# Controller.net
KiCad netlist of a schematic drawn in EAGLE
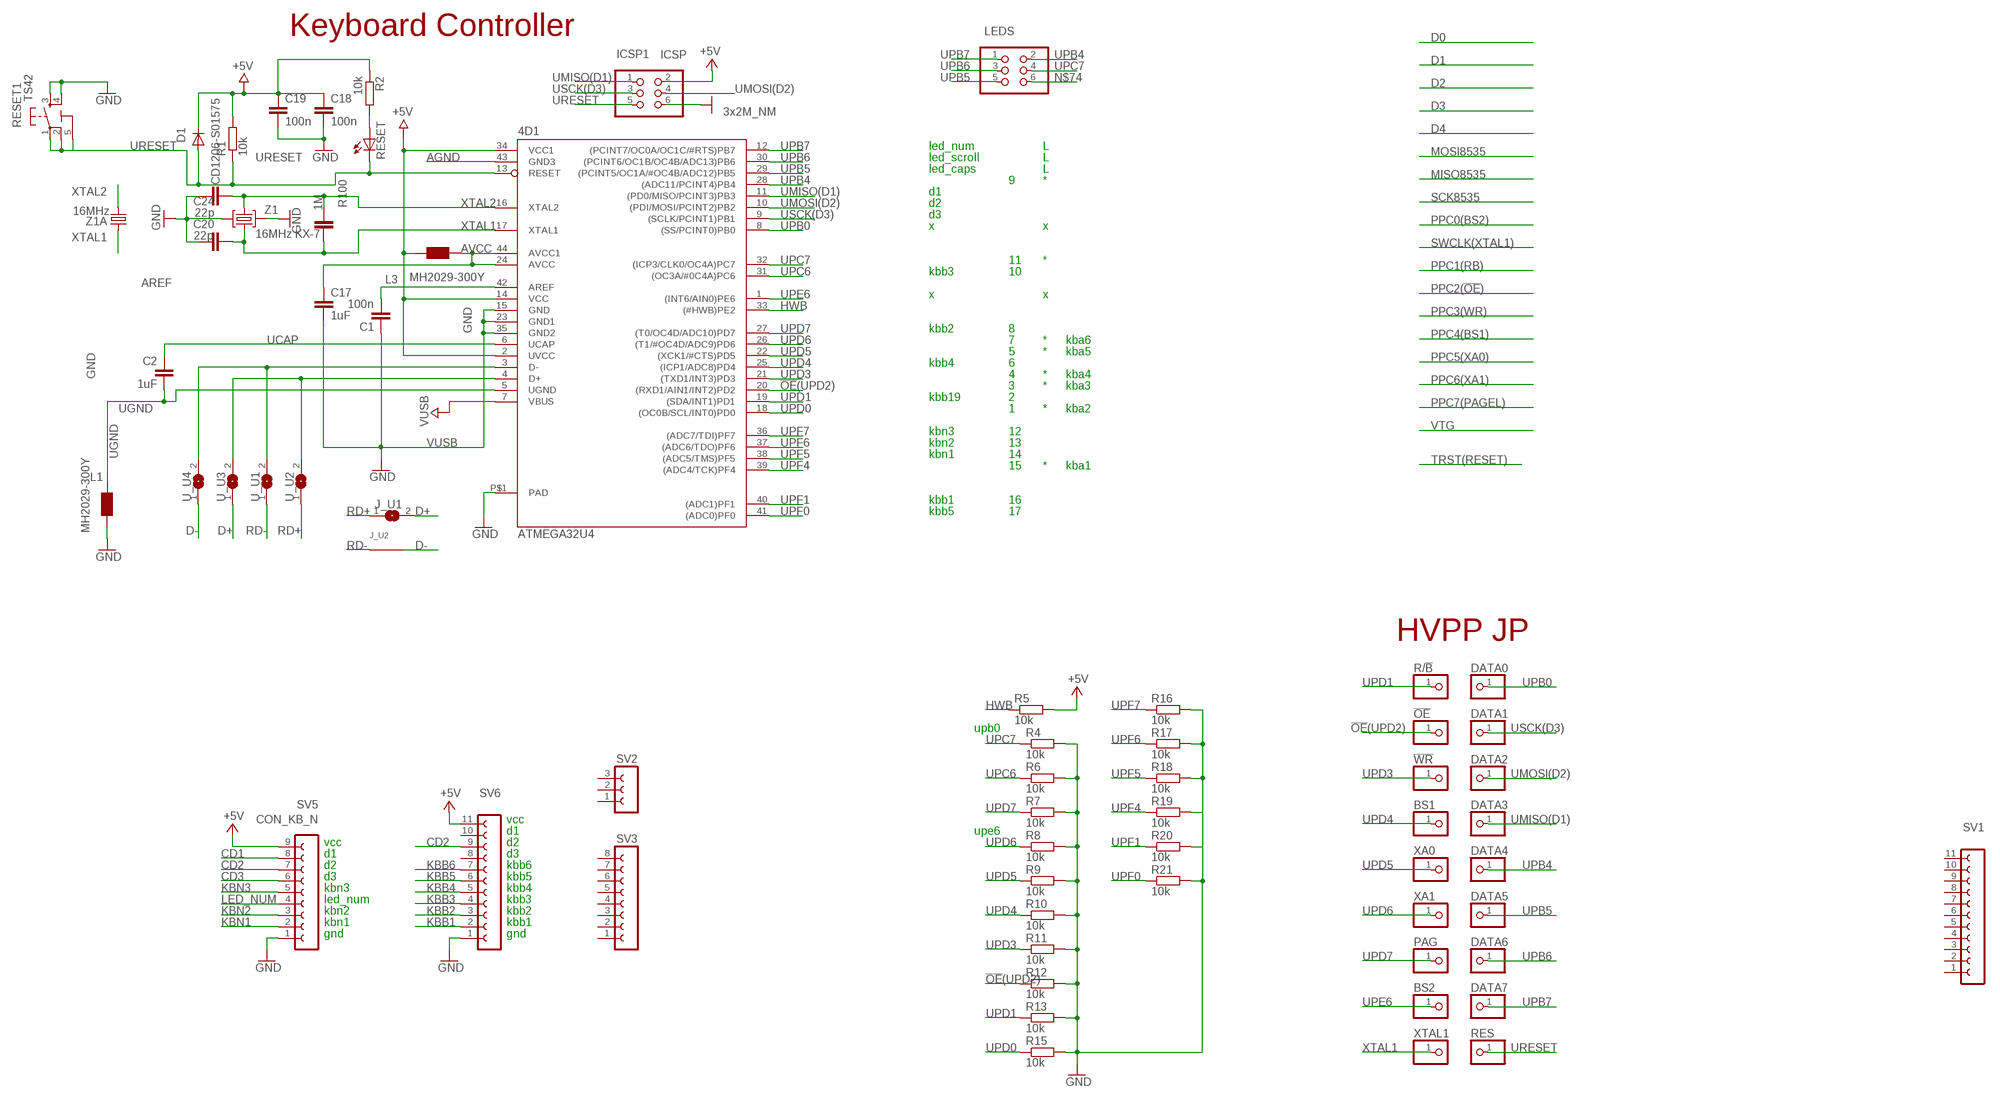
[diagram p0: schematic, sheet 1, part 1 of 2]
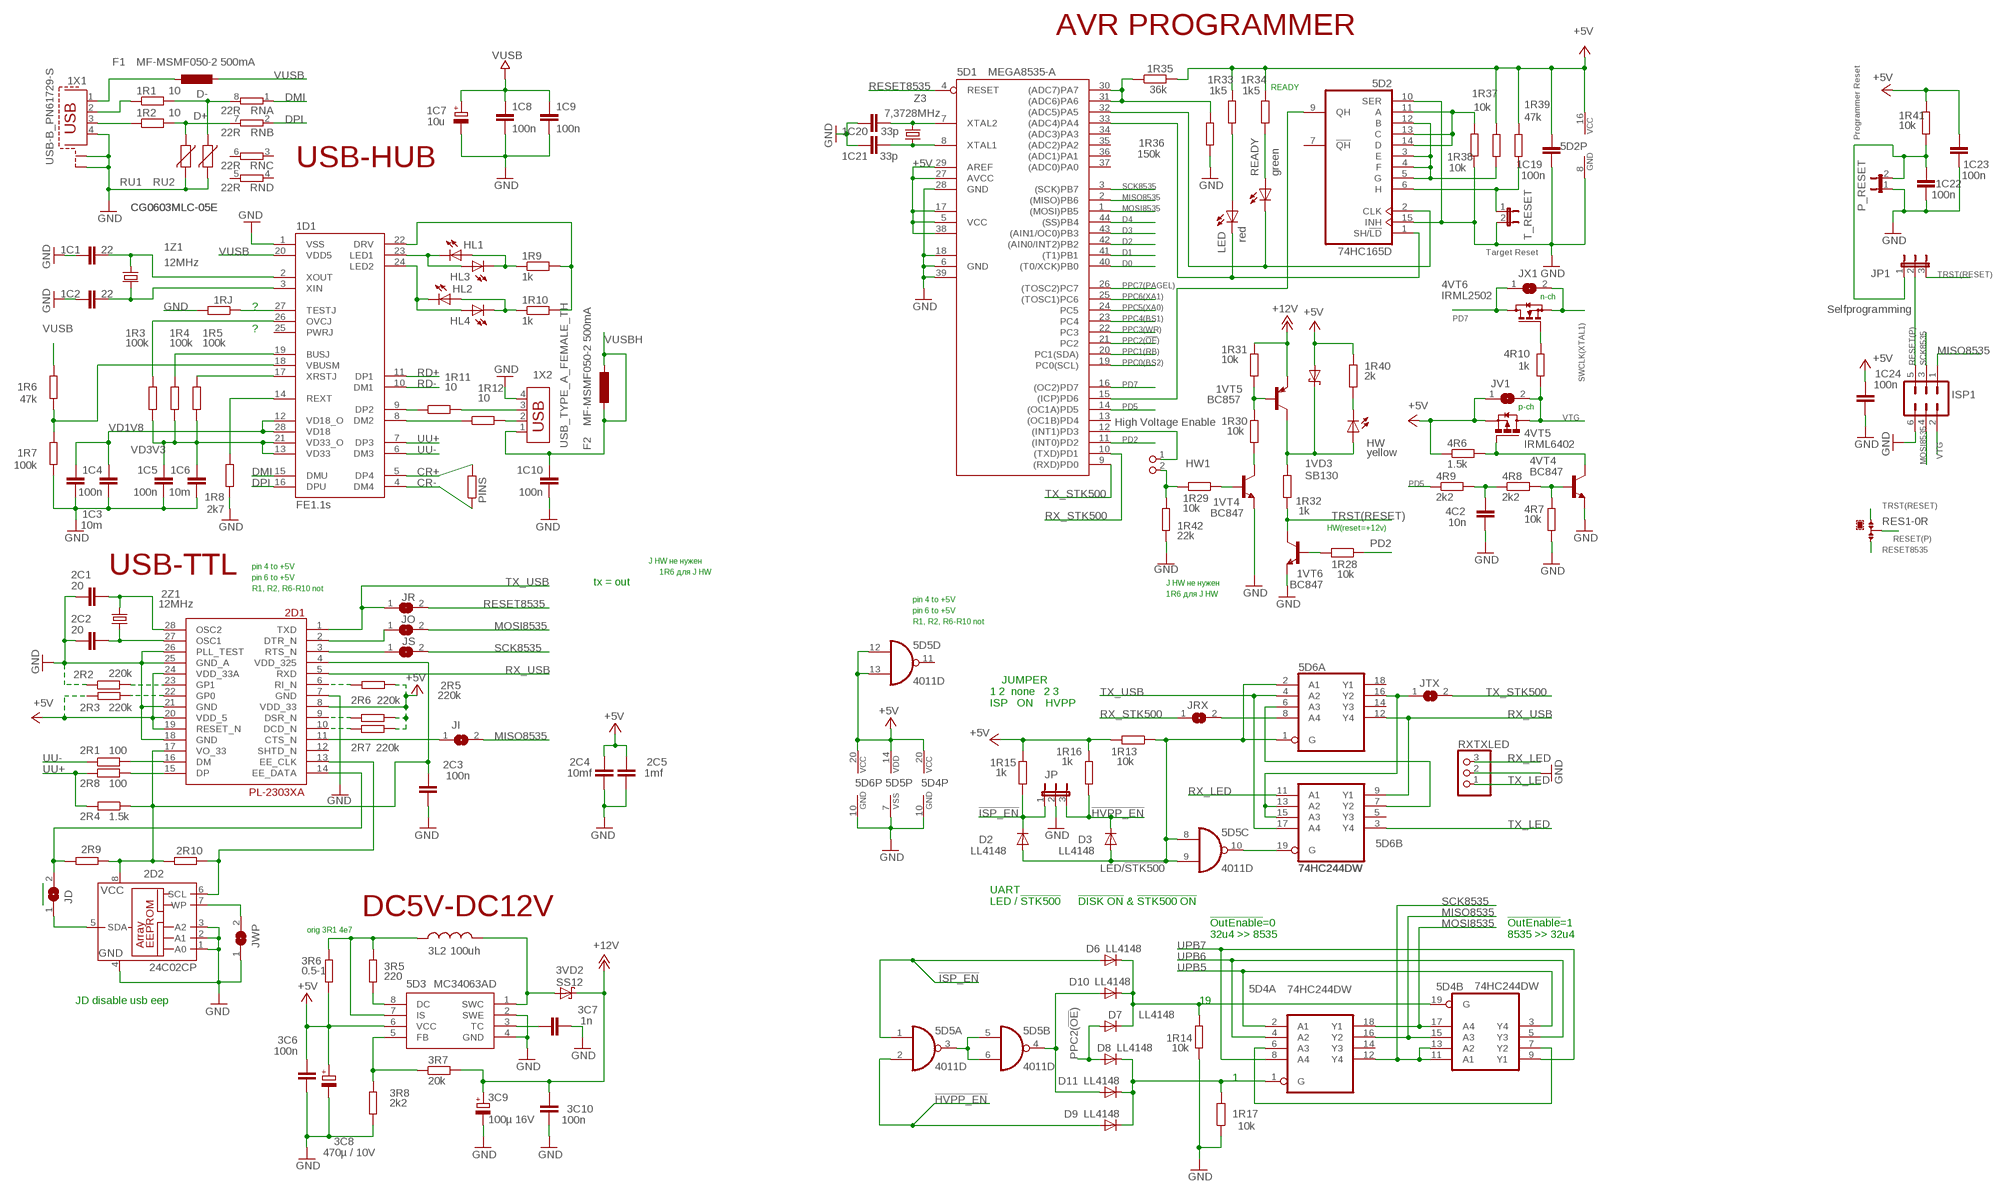
[diagram p1: schematic, sheet 1, part 2 of 2]

(export (version "E")
  (design (tool "Eeschema 10.0.6"))
  (components
    (comp (ref "!OE")
      (value "PINHD-1X1")
      (footprint "eagle-import:1X01")
      (libsource (lib "eagle-import") (part "PINHD-1X1"))
    )
    (comp (ref "!WR")
      (value "PINHD-1X1")
      (footprint "eagle-import:1X01")
      (libsource (lib "eagle-import") (part "PINHD-1X1"))
    )
    (comp (ref "1C1")
      (value "22")
      (footprint "eagle-import:C0603")
      (libsource (lib "eagle-import") (part "rcl_C-EUC0603"))
    )
    (comp (ref "1C2")
      (value "22")
      (footprint "eagle-import:C0603")
      (libsource (lib "eagle-import") (part "rcl_C-EUC0603"))
    )
    (comp (ref "1C3")
      (value "10m")
      (footprint "eagle-import:C1206")
      (libsource (lib "eagle-import") (part "rcl_C-EUC1206"))
    )
    (comp (ref "1C4")
      (value "100n")
      (footprint "eagle-import:C0805")
      (libsource (lib "eagle-import") (part "rcl_C-EUC0805"))
    )
    (comp (ref "1C5")
      (value "100n")
      (footprint "eagle-import:C0805")
      (libsource (lib "eagle-import") (part "rcl_C-EUC0805"))
    )
    (comp (ref "1C6")
      (value "10m")
      (footprint "eagle-import:C1206")
      (libsource (lib "eagle-import") (part "rcl_C-EUC1206"))
    )
    (comp (ref "1C7")
      (value "10u")
      (footprint "eagle-import:SMC_B")
      (libsource (lib "eagle-import") (part "CPOL-EUSMCB"))
    )
    (comp (ref "1C8")
      (value "100n")
      (footprint "eagle-import:C0805")
      (libsource (lib "eagle-import") (part "rcl_C-EUC0805"))
    )
    (comp (ref "1C9")
      (value "100n")
      (footprint "eagle-import:C0805")
      (libsource (lib "eagle-import") (part "rcl_C-EUC0805"))
    )
    (comp (ref "1C10")
      (value "100n")
      (footprint "eagle-import:C0805")
      (libsource (lib "eagle-import") (part "rcl_C-EUC0805"))
    )
    (comp (ref "1C19")
      (value "100n")
      (footprint "eagle-import:C0805")
      (libsource (lib "eagle-import") (part "rcl_C-EUC0805"))
    )
    (comp (ref "1C20")
      (value "33p")
      (footprint "eagle-import:C0805")
      (libsource (lib "eagle-import") (part "rcl_C-EUC0805"))
    )
    (comp (ref "1C21")
      (value "33p")
      (footprint "eagle-import:C0805")
      (libsource (lib "eagle-import") (part "rcl_C-EUC0805"))
    )
    (comp (ref "1C22")
      (value "100n")
      (footprint "eagle-import:C0805")
      (libsource (lib "eagle-import") (part "rcl_C-EUC0805"))
    )
    (comp (ref "1C23")
      (value "100n")
      (footprint "eagle-import:C0805")
      (libsource (lib "eagle-import") (part "rcl_C-EUC0805"))
    )
    (comp (ref "1C24")
      (value "100n")
      (footprint "eagle-import:C0805")
      (libsource (lib "eagle-import") (part "rcl_C-EUC0805"))
    )
    (comp (ref "1D1")
      (value "FE1.1S")
      (footprint "eagle-import:FE1.1S_SSOP-28")
      (libsource (lib "eagle-import") (part "FE1.1S"))
    )
    (comp (ref "1R1")
      (value "10")
      (footprint "eagle-import:R0603")
      (libsource (lib "eagle-import") (part "rcl_R-EU_R0603"))
    )
    (comp (ref "1R2")
      (value "10")
      (footprint "eagle-import:R0603")
      (libsource (lib "eagle-import") (part "rcl_R-EU_R0603"))
    )
    (comp (ref "1R3")
      (value "100k")
      (footprint "eagle-import:R0805")
      (libsource (lib "eagle-import") (part "rcl_R-EU_R0805"))
    )
    (comp (ref "1R4")
      (value "100k")
      (footprint "eagle-import:R0805")
      (libsource (lib "eagle-import") (part "rcl_R-EU_R0805"))
    )
    (comp (ref "1R5")
      (value "100k")
      (footprint "eagle-import:R1206W")
      (libsource (lib "eagle-import") (part "rcl_R-EU_R1206W"))
    )
    (comp (ref "1R6")
      (value "47k")
      (footprint "eagle-import:R1206W")
      (libsource (lib "eagle-import") (part "rcl_R-EU_R1206W"))
    )
    (comp (ref "1R7")
      (value "100k")
      (footprint "eagle-import:R0805")
      (libsource (lib "eagle-import") (part "rcl_R-EU_R0805"))
    )
    (comp (ref "1R8")
      (value "2k7")
      (footprint "eagle-import:R0805")
      (libsource (lib "eagle-import") (part "rcl_R-EU_R0805"))
    )
    (comp (ref "1R9")
      (value "1k")
      (footprint "eagle-import:R0805")
      (libsource (lib "eagle-import") (part "rcl_R-EU_R0805"))
    )
    (comp (ref "1R10")
      (value "1k")
      (footprint "eagle-import:R0805")
      (libsource (lib "eagle-import") (part "rcl_R-EU_R0805"))
    )
    (comp (ref "1R11")
      (value "10")
      (footprint "eagle-import:R0603")
      (libsource (lib "eagle-import") (part "rcl_R-EU_R0603"))
    )
    (comp (ref "1R12")
      (value "10")
      (footprint "eagle-import:R0603")
      (libsource (lib "eagle-import") (part "rcl_R-EU_R0603"))
    )
    (comp (ref "1R13")
      (value "10k")
      (footprint "eagle-import:M0805")
      (libsource (lib "eagle-import") (part "rcl_R-EU_M0805"))
    )
    (comp (ref "1R14")
      (value "10k")
      (footprint "eagle-import:M0805")
      (libsource (lib "eagle-import") (part "rcl_R-EU_M0805"))
    )
    (comp (ref "1R15")
      (value "1k")
      (footprint "eagle-import:M0805")
      (libsource (lib "eagle-import") (part "rcl_R-EU_M0805"))
    )
    (comp (ref "1R16")
      (value "1k")
      (footprint "eagle-import:M0805")
      (libsource (lib "eagle-import") (part "rcl_R-EU_M0805"))
    )
    (comp (ref "1R17")
      (value "10k")
      (footprint "eagle-import:M0805")
      (libsource (lib "eagle-import") (part "rcl_R-EU_M0805"))
    )
    (comp (ref "1R28")
      (value "10k")
      (footprint "eagle-import:R0805")
      (libsource (lib "eagle-import") (part "rcl_R-EU_R0805"))
    )
    (comp (ref "1R29")
      (value "10k")
      (footprint "eagle-import:M0805")
      (libsource (lib "eagle-import") (part "rcl_R-EU_M0805"))
    )
    (comp (ref "1R30")
      (value "10k")
      (footprint "eagle-import:M0805")
      (libsource (lib "eagle-import") (part "rcl_R-EU_M0805"))
    )
    (comp (ref "1R31")
      (value "10k")
      (footprint "eagle-import:M0805")
      (libsource (lib "eagle-import") (part "rcl_R-EU_M0805"))
    )
    (comp (ref "1R32")
      (value "1k")
      (footprint "eagle-import:M0805")
      (libsource (lib "eagle-import") (part "rcl_R-EU_M0805"))
    )
    (comp (ref "1R33")
      (value "1k5")
      (footprint "eagle-import:M0805")
      (libsource (lib "eagle-import") (part "rcl_R-EU_M0805"))
    )
    (comp (ref "1R34")
      (value "1k5")
      (footprint "eagle-import:M0805")
      (libsource (lib "eagle-import") (part "rcl_R-EU_M0805"))
    )
    (comp (ref "1R35")
      (value "36k")
      (footprint "eagle-import:M0805")
      (libsource (lib "eagle-import") (part "rcl_R-EU_M0805"))
    )
    (comp (ref "1R36")
      (value "150k")
      (footprint "eagle-import:R1206")
      (libsource (lib "eagle-import") (part "rcl_R-EU_R1206"))
    )
    (comp (ref "1R37")
      (value "10k")
      (footprint "eagle-import:M0805")
      (libsource (lib "eagle-import") (part "rcl_R-EU_M0805"))
    )
    (comp (ref "1R38")
      (value "10k")
      (footprint "eagle-import:M0805")
      (libsource (lib "eagle-import") (part "rcl_R-EU_M0805"))
    )
    (comp (ref "1R39")
      (value "47k")
      (footprint "eagle-import:M0805")
      (libsource (lib "eagle-import") (part "rcl_R-EU_M0805"))
    )
    (comp (ref "1R40")
      (value "2k")
      (footprint "eagle-import:R1206W")
      (libsource (lib "eagle-import") (part "rcl_R-EU_R1206W"))
    )
    (comp (ref "1R41")
      (value "10k")
      (footprint "eagle-import:M0805")
      (libsource (lib "eagle-import") (part "rcl_R-EU_M0805"))
    )
    (comp (ref "1R42")
      (value "22k")
      (footprint "eagle-import:M1206")
      (libsource (lib "eagle-import") (part "rcl_R-EU_M1206"))
    )
    (comp (ref "1RJ")
      (value "R-EU_R0805")
      (footprint "eagle-import:R0805")
      (libsource (lib "eagle-import") (part "rcl_R-EU_R0805"))
    )
    (comp (ref "1VD3")
      (value "SB130")
      (footprint "eagle-import:SMB")
      (libsource (lib "eagle-import") (part "SCHOTTKY-DIODESMD"))
    )
    (comp (ref "1VT4")
      (value "BC847")
      (footprint "eagle-import:SOT23")
      (libsource (lib "eagle-import") (part "BC847"))
    )
    (comp (ref "1VT5")
      (value "BC857")
      (footprint "eagle-import:SOT23-BEC")
      (libsource (lib "eagle-import") (part "-PNP-SOT23-BECBC857A"))
    )
    (comp (ref "1VT6")
      (value "BC847")
      (footprint "eagle-import:SOT23")
      (libsource (lib "eagle-import") (part "BC847"))
    )
    (comp (ref "1X1")
      (value "USB-B_PN61729-S")
      (footprint "eagle-import:USB-B_PN61729-S")
      (libsource (lib "eagle-import") (part "USB-B_PN61729-S"))
    )
    (comp (ref "1X2")
      (value "USB_TYPE_A_FEMALE_TH")
      (footprint "eagle-import:USB_TYPE_A_FEMALE_TH")
      (libsource (lib "eagle-import") (part "USB_TYPE_A_FEMALE_TH"))
    )
    (comp (ref "1Z1")
      (value "12MHz")
      (footprint "eagle-import:HC49_S")
      (fields (field (name "OC_FARNELL") "1667008") (field (name "OC_NEWARK") "unknown"))
      (libsource (lib "eagle-import") (part "CRYSTALHC49S"))
    )
    (comp (ref "2C1")
      (value "20")
      (footprint "eagle-import:C0805")
      (libsource (lib "eagle-import") (part "resistor_C-EUC0805"))
    )
    (comp (ref "2C2")
      (value "20")
      (footprint "eagle-import:C0805")
      (libsource (lib "eagle-import") (part "resistor_C-EUC0805"))
    )
    (comp (ref "2C3")
      (value "100n")
      (footprint "eagle-import:C0805")
      (libsource (lib "eagle-import") (part "resistor_C-EUC0805"))
    )
    (comp (ref "2C4")
      (value "10mf")
      (footprint "eagle-import:C1210")
      (libsource (lib "eagle-import") (part "rcl_C-EUC1210"))
    )
    (comp (ref "2C5")
      (value "1mf")
      (footprint "eagle-import:C0805")
      (libsource (lib "eagle-import") (part "rcl_C-EUC0805"))
    )
    (comp (ref "2D1")
      (value "PL-2303XA")
      (footprint "eagle-import:SSOP28DB")
      (libsource (lib "eagle-import") (part "PL-2303XA"))
    )
    (comp (ref "2D2")
      (value "24C02CP")
      (footprint "eagle-import:DIL8")
      (fields
        (field (name "MF") "MICROCHIP")
        (field (name "MPN") "24C02C/P")
        (field (name "MPN_1") "24C02C/P")
        (field (name "OC_FARNELL") "1296567")
        (field (name "OC_NEWARK") "96K4064")
      )
      (libsource (lib "eagle-import") (part "24CP02C"))
    )
    (comp (ref "2R1")
      (value "100")
      (footprint "eagle-import:R0603")
      (libsource (lib "eagle-import") (part "resistor_R-EU_R0603"))
    )
    (comp (ref "2R2")
      (value "220k")
      (footprint "eagle-import:R0603")
      (libsource (lib "eagle-import") (part "resistor_R-EU_R0603"))
    )
    (comp (ref "2R3")
      (value "220k")
      (footprint "eagle-import:R1206W")
      (libsource (lib "eagle-import") (part "resistor_R-EU_R1206W"))
    )
    (comp (ref "2R4")
      (value "1.5k")
      (footprint "eagle-import:R0603")
      (libsource (lib "eagle-import") (part "resistor_R-EU_R0603"))
    )
    (comp (ref "2R5")
      (value "220k")
      (footprint "eagle-import:R1206W")
      (libsource (lib "eagle-import") (part "resistor_R-EU_R1206W"))
    )
    (comp (ref "2R6")
      (value "220k")
      (footprint "eagle-import:R0603")
      (libsource (lib "eagle-import") (part "resistor_R-EU_R0603"))
    )
    (comp (ref "2R7")
      (value "220k")
      (footprint "eagle-import:R0603")
      (libsource (lib "eagle-import") (part "resistor_R-EU_R0603"))
    )
    (comp (ref "2R8")
      (value "100")
      (footprint "eagle-import:R0603")
      (libsource (lib "eagle-import") (part "resistor_R-EU_R0603"))
    )
    (comp (ref "2R9")
      (value "R-EU_R0805")
      (footprint "eagle-import:R0805")
      (libsource (lib "eagle-import") (part "R-EU_R0805"))
    )
    (comp (ref "2R10")
      (value "R-EU_R0805")
      (footprint "eagle-import:R0805")
      (libsource (lib "eagle-import") (part "R-EU_R0805"))
    )
    (comp (ref "2Z1")
      (value "12MHz")
      (footprint "eagle-import:HC49_S")
      (libsource (lib "eagle-import") (part "CRYSTALHC49S"))
    )
    (comp (ref "3C6")
      (value "100n")
      (footprint "eagle-import:C025-024X044")
      (libsource (lib "eagle-import") (part "rc-elektronik_C-EU025-024X044"))
    )
    (comp (ref "3C7")
      (value "1n")
      (footprint "eagle-import:C025-025X050")
      (libsource (lib "eagle-import") (part "rcl_C-EU025-025X050"))
    )
    (comp (ref "3C8")
      (value "470µ / 10V")
      (footprint "eagle-import:RCL_E3,5-8")
      (libsource (lib "eagle-import") (part "RCL_CPOL-EUE3.5-8"))
    )
    (comp (ref "3C9")
      (value "100µ 16V")
      (footprint "eagle-import:RCL_E3,5-8")
      (libsource (lib "eagle-import") (part "RCL_CPOL-EUE3.5-8"))
    )
    (comp (ref "3C10")
      (value "100n")
      (footprint "eagle-import:C025-025X050")
      (libsource (lib "eagle-import") (part "rcl_C-EU025-025X050"))
    )
    (comp (ref "3L2")
      (value "100uh")
      (footprint "eagle-import:0207_10")
      (libsource (lib "eagle-import") (part "L-US0207/10"))
    )
    (comp (ref "3R5")
      (value "220")
      (footprint "eagle-import:R1206")
      (libsource (lib "eagle-import") (part "rcl_R-EU_R1206"))
    )
    (comp (ref "3R6")
      (value "0.5-1")
      (footprint "eagle-import:M1206")
      (libsource (lib "eagle-import") (part "rcl_R-EU_M1206"))
    )
    (comp (ref "3R7")
      (value "20k")
      (footprint "eagle-import:M0805")
      (libsource (lib "eagle-import") (part "rcl_R-EU_M0805"))
    )
    (comp (ref "3R8")
      (value "2k2")
      (footprint "eagle-import:M0805")
      (libsource (lib "eagle-import") (part "rcl_R-EU_M0805"))
    )
    (comp (ref "3VD2")
      (value "SS12")
      (footprint "eagle-import:SMB")
      (libsource (lib "eagle-import") (part "SCHOTTKY-DIODESMD"))
    )
    (comp (ref "4C2")
      (value "10n")
      (footprint "eagle-import:C1206")
      (libsource (lib "eagle-import") (part "rcl_C-EUC1206"))
    )
    (comp (ref "4D1")
      (value "ATMEGA32U4")
      (footprint "eagle-import:SMARTPRJ_TQFP44-PAD")
      (libsource (lib "eagle-import") (part "SMARTPRJ_ATMEGA32U4-XUAU"))
    )
    (comp (ref "4R6")
      (value "1.5k")
      (footprint "eagle-import:M0805")
      (libsource (lib "eagle-import") (part "rcl_R-EU_M0805"))
    )
    (comp (ref "4R7")
      (value "10k")
      (footprint "eagle-import:M0805")
      (libsource (lib "eagle-import") (part "rcl_R-EU_M0805"))
    )
    (comp (ref "4R8")
      (value "2k2")
      (footprint "eagle-import:M1206")
      (libsource (lib "eagle-import") (part "rcl_R-EU_M1206"))
    )
    (comp (ref "4R9")
      (value "2k2")
      (footprint "eagle-import:M0805")
      (libsource (lib "eagle-import") (part "rcl_R-EU_M0805"))
    )
    (comp (ref "4R10")
      (value "1k")
      (footprint "eagle-import:M0805")
      (libsource (lib "eagle-import") (part "rcl_R-EU_M0805"))
    )
    (comp (ref "4VT4")
      (value "BC847")
      (footprint "eagle-import:SOT23")
      (libsource (lib "eagle-import") (part "transistor-neu-to92_BC847"))
    )
    (comp (ref "4VT5")
      (value "IRML6402")
      (footprint "eagle-import:SUPER-SOT3")
      (libsource (lib "eagle-import") (part "FDN360P"))
    )
    (comp (ref "4VT6")
      (value "IRML2502")
      (footprint "eagle-import:SOT23")
      (libsource (lib "eagle-import") (part "BSS123"))
    )
    (comp (ref "5D1")
      (value "MEGA8535-A")
      (footprint "eagle-import:TQFP44")
      (fields (field (name "MPN") "ATMEGA8535-16AU"))
      (libsource (lib "eagle-import") (part "MEGA8535-A"))
    )
    (comp (ref "5D2")
      (value "74HC165D")
      (footprint "eagle-import:SO16")
      (libsource (lib "eagle-import") (part "74165DHC"))
    )
    (comp (ref "5D3")
      (value "MC34063AD")
      (footprint "eagle-import:SOIC8")
      (libsource (lib "eagle-import") (part "MC34063AD"))
    )
    (comp (ref "5D4")
      (value "74HC244DW")
      (footprint "eagle-import:SO20W")
      (libsource (lib "eagle-import") (part "74244DWHC"))
    )
    (comp (ref "5D5")
      (value "4011D")
      (footprint "eagle-import:SO14")
      (libsource (lib "eagle-import") (part "4011D"))
    )
    (comp (ref "5D6")
      (value "74HC244DW")
      (footprint "eagle-import:SO20W")
      (libsource (lib "eagle-import") (part "74244DWHC"))
    )
    (comp (ref "BS1")
      (value "PINHD-1X1")
      (footprint "eagle-import:1X01")
      (libsource (lib "eagle-import") (part "PINHD-1X1"))
    )
    (comp (ref "BS2")
      (value "PINHD-1X1")
      (footprint "eagle-import:1X01")
      (libsource (lib "eagle-import") (part "PINHD-1X1"))
    )
    (comp (ref "C1")
      (value "100n")
      (footprint "eagle-import:C0603-ROUND")
      (libsource (lib "eagle-import") (part "C-EUC0603"))
    )
    (comp (ref "C2")
      (value "1uF")
      (footprint "eagle-import:C0603")
      (libsource (lib "eagle-import") (part "rcl_C-EUC0603"))
    )
    (comp (ref "C17")
      (value "1uF")
      (footprint "eagle-import:C0603-ROUND")
      (libsource (lib "eagle-import") (part "C-EUC0603"))
    )
    (comp (ref "C18")
      (value "100n")
      (footprint "eagle-import:C0603")
      (libsource (lib "eagle-import") (part "rcl_C-EUC0603"))
    )
    (comp (ref "C19")
      (value "100n")
      (footprint "eagle-import:C0603-ROUND")
      (libsource (lib "eagle-import") (part "C-EUC0603"))
    )
    (comp (ref "C20")
      (value "22p")
      (footprint "eagle-import:C0603")
      (libsource (lib "eagle-import") (part "rcl_C-EUC0603"))
    )
    (comp (ref "C24")
      (value "22p")
      (footprint "eagle-import:C0603")
      (libsource (lib "eagle-import") (part "rcl_C-EUC0603"))
    )
    (comp (ref "D1")
      (value "CD1206-S01575")
      (footprint "eagle-import:MINIMELF")
      (libsource (lib "eagle-import") (part "DIODE-MINIMELF"))
    )
    (comp (ref "D2")
      (value "LL4148")
      (footprint "eagle-import:SOD80C")
      (libsource (lib "eagle-import") (part "LL4148"))
    )
    (comp (ref "D3")
      (value "LL4148")
      (footprint "eagle-import:SOD80C")
      (libsource (lib "eagle-import") (part "LL4148"))
    )
    (comp (ref "D6")
      (value "LL4148")
      (footprint "eagle-import:SOD80C")
      (libsource (lib "eagle-import") (part "LL4148"))
    )
    (comp (ref "D7")
      (value "LL4148")
      (footprint "eagle-import:SOD80C")
      (libsource (lib "eagle-import") (part "LL4148"))
    )
    (comp (ref "D8")
      (value "LL4148")
      (footprint "eagle-import:SOD80C")
      (libsource (lib "eagle-import") (part "LL4148"))
    )
    (comp (ref "D9")
      (value "LL4148")
      (footprint "eagle-import:SOD80C")
      (libsource (lib "eagle-import") (part "LL4148"))
    )
    (comp (ref "D10")
      (value "LL4148")
      (footprint "eagle-import:SOD80C")
      (libsource (lib "eagle-import") (part "LL4148"))
    )
    (comp (ref "D11")
      (value "LL4148")
      (footprint "eagle-import:SOD80C")
      (libsource (lib "eagle-import") (part "LL4148"))
    )
    (comp (ref "DATA0")
      (value "PINHD-1X1")
      (footprint "eagle-import:1X01")
      (libsource (lib "eagle-import") (part "PINHD-1X1"))
    )
    (comp (ref "DATA1")
      (value "PINHD-1X1")
      (footprint "eagle-import:1X01")
      (libsource (lib "eagle-import") (part "PINHD-1X1"))
    )
    (comp (ref "DATA2")
      (value "PINHD-1X1")
      (footprint "eagle-import:1X01")
      (libsource (lib "eagle-import") (part "PINHD-1X1"))
    )
    (comp (ref "DATA3")
      (value "PINHD-1X1")
      (footprint "eagle-import:1X01")
      (libsource (lib "eagle-import") (part "PINHD-1X1"))
    )
    (comp (ref "DATA4")
      (value "PINHD-1X1")
      (footprint "eagle-import:1X01")
      (libsource (lib "eagle-import") (part "PINHD-1X1"))
    )
    (comp (ref "DATA5")
      (value "PINHD-1X1")
      (footprint "eagle-import:1X01")
      (libsource (lib "eagle-import") (part "PINHD-1X1"))
    )
    (comp (ref "DATA6")
      (value "PINHD-1X1")
      (footprint "eagle-import:1X01")
      (libsource (lib "eagle-import") (part "PINHD-1X1"))
    )
    (comp (ref "DATA7")
      (value "PINHD-1X1")
      (footprint "eagle-import:1X01")
      (libsource (lib "eagle-import") (part "PINHD-1X1"))
    )
    (comp (ref "F1")
      (value "MF-MSMF050-2 500mA")
      (footprint "eagle-import:L1812")
      (libsource (lib "eagle-import") (part "L-EUL1812"))
    )
    (comp (ref "F2")
      (value "MF-MSMF050-2 500mA")
      (footprint "eagle-import:L1812")
      (libsource (lib "eagle-import") (part "L-EUL1812"))
    )
    (comp (ref "HL1")
      (value "LEDSML0603")
      (footprint "eagle-import:SML0603")
      (libsource (lib "eagle-import") (part "LEDSML0603"))
    )
    (comp (ref "HL2")
      (value "LEDSML0603")
      (footprint "eagle-import:SML0603")
      (libsource (lib "eagle-import") (part "LEDSML0603"))
    )
    (comp (ref "HL3")
      (value "LEDSML0603")
      (footprint "eagle-import:SML0603")
      (libsource (lib "eagle-import") (part "LEDSML0603"))
    )
    (comp (ref "HL4")
      (value "LEDSML0603")
      (footprint "eagle-import:SML0603")
      (libsource (lib "eagle-import") (part "LEDSML0603"))
    )
    (comp (ref "HW")
      (value "yellow")
      (footprint "eagle-import:SML0603")
      (libsource (lib "eagle-import") (part "LEDSML0603"))
    )
    (comp (ref "HW1")
      (value "High Voltage Enable")
      (footprint "eagle-import:PINHEAD_1X02")
      (libsource (lib "eagle-import") (part "PINHEAD_PINHD-1X2"))
    )
    (comp (ref "ICSP1")
      (value "ICSP")
      (footprint "eagle-import:2X03")
      (libsource (lib "eagle-import") (part "PINHD-2X3"))
    )
    (comp (ref "ISP1")
      (value "MA03-2")
      (footprint "eagle-import:MA03-2")
      (libsource (lib "eagle-import") (part "MA03-2"))
    )
    (comp (ref "JD") (value "SJ") (footprint "eagle-import:SJ") (libsource (lib "eagle-import") (part "SJ")))
    (comp (ref "JI") (value "SJ") (footprint "eagle-import:SJ") (libsource (lib "eagle-import") (part "SJ")))
    (comp (ref "JO") (value "SJ") (footprint "eagle-import:SJ") (libsource (lib "eagle-import") (part "SJ")))
    (comp (ref "JP")
      (value "JP2E")
      (footprint "eagle-import:JP2")
      (libsource (lib "eagle-import") (part "JP2E"))
    )
    (comp (ref "JP1")
      (value "Selfprogramming")
      (footprint "eagle-import:JUMPER_JP2")
      (libsource (lib "eagle-import") (part "JUMPER_JP2E"))
    )
    (comp (ref "JR") (value "SJ") (footprint "eagle-import:SJ") (libsource (lib "eagle-import") (part "SJ")))
    (comp (ref "JRX") (value "SJ") (footprint "eagle-import:SJ") (libsource (lib "eagle-import") (part "SJ")))
    (comp (ref "JS") (value "SJ") (footprint "eagle-import:SJ") (libsource (lib "eagle-import") (part "SJ")))
    (comp (ref "JTX") (value "SJ") (footprint "eagle-import:SJ") (libsource (lib "eagle-import") (part "SJ")))
    (comp (ref "JV1") (value "SJ") (footprint "eagle-import:SJ") (libsource (lib "eagle-import") (part "SJ")))
    (comp (ref "JWP") (value "SJ") (footprint "eagle-import:SJ") (libsource (lib "eagle-import") (part "SJ")))
    (comp (ref "JX1") (value "SJ") (footprint "eagle-import:SJ") (libsource (lib "eagle-import") (part "SJ")))
    (comp (ref "J_U1")
      (value "SJ")
      (footprint "eagle-import:SJ")
      (libsource (lib "eagle-import") (part "SJ"))
    )
    (comp (ref "J_U2")
      (value "J")
      (footprint "eagle-import:R1206W")
      (libsource (lib "eagle-import") (part "J"))
    )
    (comp (ref "L1")
      (value "MH2029-300Y")
      (footprint "eagle-import:0805")
      (libsource (lib "eagle-import") (part "WE-CBF_0805"))
    )
    (comp (ref "L3")
      (value "MH2029-300Y")
      (footprint "eagle-import:0805")
      (libsource (lib "eagle-import") (part "WE-CBF_0805"))
    )
    (comp (ref "LED")
      (value "red")
      (footprint "eagle-import:SML0603")
      (libsource (lib "eagle-import") (part "LEDSML0603"))
    )
    (comp (ref "LEDS")
      (value "PINHD-2X3")
      (footprint "eagle-import:2X03")
      (libsource (lib "eagle-import") (part "PINHD-2X3"))
    )
    (comp (ref "PAG")
      (value "PINHD-1X1")
      (footprint "eagle-import:1X01")
      (libsource (lib "eagle-import") (part "PINHD-1X1"))
    )
    (comp (ref "PINS")
      (value "R-EU_R0805")
      (footprint "eagle-import:R0805")
      (libsource (lib "eagle-import") (part "rcl_R-EU_R0805"))
    )
    (comp (ref "P_RESET")
      (value "JP1E")
      (footprint "eagle-import:JP1")
      (libsource (lib "eagle-import") (part "JP1E"))
    )
    (comp (ref "R/!B")
      (value "PINHD-1X1")
      (footprint "eagle-import:1X01")
      (libsource (lib "eagle-import") (part "PINHD-1X1"))
    )
    (comp (ref "R1")
      (value "10k")
      (footprint "eagle-import:M0805")
      (libsource (lib "eagle-import") (part "rcl_R-EU_M0805"))
    )
    (comp (ref "R2")
      (value "10k")
      (footprint "eagle-import:M0805")
      (libsource (lib "eagle-import") (part "rcl_R-EU_M0805"))
    )
    (comp (ref "R4")
      (value "10k")
      (footprint "eagle-import:M0805")
      (libsource (lib "eagle-import") (part "rcl_R-EU_M0805"))
    )
    (comp (ref "R5")
      (value "10k")
      (footprint "eagle-import:M1206")
      (libsource (lib "eagle-import") (part "rcl_R-EU_M1206"))
    )
    (comp (ref "R6")
      (value "10k")
      (footprint "eagle-import:M0805")
      (libsource (lib "eagle-import") (part "rcl_R-EU_M0805"))
    )
    (comp (ref "R7")
      (value "10k")
      (footprint "eagle-import:M0805")
      (libsource (lib "eagle-import") (part "rcl_R-EU_M0805"))
    )
    (comp (ref "R8")
      (value "10k")
      (footprint "eagle-import:M0805")
      (libsource (lib "eagle-import") (part "rcl_R-EU_M0805"))
    )
    (comp (ref "R9")
      (value "10k")
      (footprint "eagle-import:M0805")
      (libsource (lib "eagle-import") (part "rcl_R-EU_M0805"))
    )
    (comp (ref "R10")
      (value "10k")
      (footprint "eagle-import:M0805")
      (libsource (lib "eagle-import") (part "rcl_R-EU_M0805"))
    )
    (comp (ref "R11")
      (value "10k")
      (footprint "eagle-import:M0805")
      (libsource (lib "eagle-import") (part "rcl_R-EU_M0805"))
    )
    (comp (ref "R12")
      (value "10k")
      (footprint "eagle-import:M0805")
      (libsource (lib "eagle-import") (part "rcl_R-EU_M0805"))
    )
    (comp (ref "R13")
      (value "10k")
      (footprint "eagle-import:M0805")
      (libsource (lib "eagle-import") (part "rcl_R-EU_M0805"))
    )
    (comp (ref "R15")
      (value "10k")
      (footprint "eagle-import:M0805")
      (libsource (lib "eagle-import") (part "rcl_R-EU_M0805"))
    )
    (comp (ref "R16")
      (value "10k")
      (footprint "eagle-import:M0805")
      (libsource (lib "eagle-import") (part "rcl_R-EU_M0805"))
    )
    (comp (ref "R17")
      (value "10k")
      (footprint "eagle-import:M0805")
      (libsource (lib "eagle-import") (part "rcl_R-EU_M0805"))
    )
    (comp (ref "R18")
      (value "10k")
      (footprint "eagle-import:M0805")
      (libsource (lib "eagle-import") (part "rcl_R-EU_M0805"))
    )
    (comp (ref "R19")
      (value "10k")
      (footprint "eagle-import:M0805")
      (libsource (lib "eagle-import") (part "rcl_R-EU_M0805"))
    )
    (comp (ref "R20")
      (value "10k")
      (footprint "eagle-import:M0805")
      (libsource (lib "eagle-import") (part "rcl_R-EU_M0805"))
    )
    (comp (ref "R21")
      (value "10k")
      (footprint "eagle-import:M0805")
      (libsource (lib "eagle-import") (part "rcl_R-EU_M0805"))
    )
    (comp (ref "R100")
      (value "1M")
      (footprint "eagle-import:C0805")
      (libsource (lib "eagle-import") (part "rcl_C-EUC0805"))
    )
    (comp (ref "READY")
      (value "green")
      (footprint "eagle-import:SML0603")
      (libsource (lib "eagle-import") (part "LEDSML0603"))
    )
    (comp (ref "RES")
      (value "PINHD-1X1")
      (footprint "eagle-import:1X01")
      (libsource (lib "eagle-import") (part "PINHD-1X1"))
    )
    (comp (ref "RES1")
      (value "0R-JUMPA")
      (footprint "eagle-import:A0R-JMP")
      (libsource (lib "eagle-import") (part "0R-JUMPA"))
    )
    (comp (ref "RESET")
      (value "LEDSML0805")
      (footprint "eagle-import:SML0805")
      (libsource (lib "eagle-import") (part "LEDSML0805"))
    )
    (comp (ref "RESET1")
      (value "TS42")
      (footprint "eagle-import:TS42")
      (libsource (lib "eagle-import") (part "TS42"))
    )
    (comp (ref "RN")
      (value "22R")
      (footprint "eagle-import:CAY16")
      (libsource (lib "eagle-import") (part "4R-NCAY16"))
    )
    (comp (ref "RU1")
      (value "CG0603MLC-05E")
      (footprint "eagle-import:CT_CN0603")
      (libsource (lib "eagle-import") (part "VARISTORCN0603"))
    )
    (comp (ref "RU2")
      (value "CG0603MLC-05E")
      (footprint "eagle-import:CT_CN0603")
      (libsource (lib "eagle-import") (part "VARISTORCN0603"))
    )
    (comp (ref "RXTXLED")
      (value "PINHD-1X3")
      (footprint "eagle-import:1X03")
      (libsource (lib "eagle-import") (part "PINHD-1X3"))
    )
    (comp (ref "SV1")
      (value "FE12-1")
      (footprint "eagle-import:FE12")
      (fields (field (name "OC_FARNELL") "unknown") (field (name "OC_NEWARK") "unknown"))
      (libsource (lib "eagle-import") (part "FE12-1"))
    )
    (comp (ref "SV2")
      (value "FE03-1")
      (footprint "eagle-import:FE03-1")
      (fields (field (name "OC_FARNELL") "unknown") (field (name "OC_NEWARK") "unknown"))
      (libsource (lib "eagle-import") (part "FE03-1"))
    )
    (comp (ref "SV3")
      (value "FE08-1")
      (footprint "eagle-import:FE08")
      (fields (field (name "OC_FARNELL") "unknown") (field (name "OC_NEWARK") "unknown"))
      (libsource (lib "eagle-import") (part "FE08-1"))
    )
    (comp (ref "SV5")
      (value "CON_KB_N")
      (footprint "eagle-import:FE09")
      (libsource (lib "eagle-import") (part "FE09-1"))
    )
    (comp (ref "SV6")
      (value "FE12-1")
      (footprint "eagle-import:FE12")
      (libsource (lib "eagle-import") (part "FE12-1"))
    )
    (comp (ref "T_RESET")
      (value "JP1E")
      (footprint "eagle-import:JP1")
      (libsource (lib "eagle-import") (part "JP1E"))
    )
    (comp (ref "U_U1")
      (value "SJ")
      (footprint "eagle-import:SJ")
      (libsource (lib "eagle-import") (part "SJ"))
    )
    (comp (ref "U_U2")
      (value "SJ")
      (footprint "eagle-import:SJ")
      (libsource (lib "eagle-import") (part "SJ"))
    )
    (comp (ref "U_U3")
      (value "SJ")
      (footprint "eagle-import:SJ")
      (libsource (lib "eagle-import") (part "SJ"))
    )
    (comp (ref "U_U4")
      (value "SJ")
      (footprint "eagle-import:SJ")
      (libsource (lib "eagle-import") (part "SJ"))
    )
    (comp (ref "XA0")
      (value "PINHD-1X1")
      (footprint "eagle-import:1X01")
      (libsource (lib "eagle-import") (part "PINHD-1X1"))
    )
    (comp (ref "XA1")
      (value "PINHD-1X1")
      (footprint "eagle-import:1X01")
      (libsource (lib "eagle-import") (part "PINHD-1X1"))
    )
    (comp (ref "XTAL1")
      (value "PINHD-1X1")
      (footprint "eagle-import:1X01")
      (libsource (lib "eagle-import") (part "PINHD-1X1"))
    )
    (comp (ref "Z1")
      (value "16MHz KX-7")
      (footprint "eagle-import:CRYSTAL-3.2-2.5")
      (libsource (lib "eagle-import") (part "CRYSTAL-3.2-2.5"))
    )
    (comp (ref "Z1A")
      (value "16MHz")
      (footprint "eagle-import:HC49_S")
      (libsource (lib "eagle-import") (part "CRYSTALHC49S"))
    )
    (comp (ref "Z3")
      (value "7,3728MHz")
      (footprint "eagle-import:HC49U-V")
      (libsource (lib "eagle-import") (part "CRYTALHC49U-V"))
    )
  )
  (nets
    (net (code "1") (name "+5V") (class "Default")
      (node (ref "1C19") (pin "1") (pinfunction "1_1") (pintype "passive"))
      (node (ref "1C23") (pin "2") (pinfunction "2_2") (pintype "passive"))
      (node (ref "1C24") (pin "2") (pinfunction "2_2") (pintype "passive"))
      (node (ref "1R13") (pin "2") (pinfunction "2_2") (pintype "passive"))
      (node (ref "1R15") (pin "2") (pinfunction "2_2") (pintype "passive"))
      (node (ref "1R16") (pin "2") (pinfunction "2_2") (pintype "passive"))
      (node (ref "1R33") (pin "2") (pinfunction "2_2") (pintype "passive"))
      (node (ref "1R34") (pin "2") (pinfunction "2_2") (pintype "passive"))
      (node (ref "1R35") (pin "2") (pinfunction "2_2") (pintype "passive"))
      (node (ref "1R37") (pin "1") (pinfunction "1_1") (pintype "passive"))
      (node (ref "1R39") (pin "1") (pinfunction "1_1") (pintype "passive"))
      (node (ref "1R40") (pin "2") (pinfunction "2_2") (pintype "passive"))
      (node (ref "1R41") (pin "2") (pinfunction "2_2") (pintype "passive"))
      (node (ref "1VD3") (pin "A") (pinfunction "A_A") (pintype "passive"))
      (node (ref "2C4") (pin "2") (pinfunction "2_2") (pintype "passive"))
      (node (ref "2C5") (pin "2") (pinfunction "2_2") (pintype "passive"))
      (node (ref "2D1") (pin "19") (pinfunction "RESET_N_19") (pintype "bidirectional"))
      (node (ref "2D1") (pin "20") (pinfunction "VDD_5_20") (pintype "bidirectional"))
      (node (ref "2D1") (pin "24") (pinfunction "VDD_33A_24") (pintype "bidirectional"))
      (node (ref "2D1") (pin "8") (pinfunction "VDD_33_8") (pintype "bidirectional"))
      (node (ref "2R3") (pin "1") (pinfunction "1_1") (pintype "passive"))
      (node (ref "2R5") (pin "2") (pinfunction "2_2") (pintype "passive"))
      (node (ref "2R6") (pin "1") (pinfunction "1_1") (pintype "passive"))
      (node (ref "2R7") (pin "1") (pinfunction "1_1") (pintype "passive"))
      (node (ref "3C6") (pin "1") (pinfunction "1_1") (pintype "passive"))
      (node (ref "3C8") (pin "+") (pinfunction "+_+") (pintype "passive"))
      (node (ref "3R6") (pin "1") (pinfunction "1_1") (pintype "passive"))
      (node (ref "4D1") (pin "14") (pinfunction "VCC_14") (pintype "power_in"))
      (node (ref "4D1") (pin "2") (pinfunction "UVCC_2") (pintype "power_in"))
      (node (ref "4D1") (pin "34") (pinfunction "VCC1_34") (pintype "power_in"))
      (node (ref "4R6") (pin "1") (pinfunction "1_1") (pintype "passive"))
      (node (ref "4VT5") (pin "2") (pinfunction "S_2") (pintype "passive"))
      (node (ref "5D1") (pin "17") (pinfunction "VCC1_17") (pintype "power_in"))
      (node (ref "5D1") (pin "27") (pinfunction "AVCC_27") (pintype "power_in"))
      (node (ref "5D1") (pin "29") (pinfunction "AREF_29") (pintype "passive"))
      (node (ref "5D1") (pin "38") (pinfunction "VCC2_38") (pintype "power_in"))
      (node (ref "5D1") (pin "5") (pinfunction "VCC_5") (pintype "power_in"))
      (node (ref "5D2") (pin "16") (pinfunction "VCC_16") (pintype "power_in"))
      (node (ref "5D3") (pin "6") (pinfunction "VCC_6") (pintype "passive"))
      (node (ref "5D4") (pin "20") (pinfunction "VCC_20") (pintype "power_in"))
      (node (ref "5D5") (pin "12") (pinfunction "I0_12") (pintype "input"))
      (node (ref "5D5") (pin "13") (pinfunction "I1_13") (pintype "input"))
      (node (ref "5D5") (pin "14") (pinfunction "VDD_14") (pintype "power_in"))
      (node (ref "5D6") (pin "20") (pinfunction "VCC_20") (pintype "power_in"))
      (node (ref "C18") (pin "1") (pinfunction "1_1") (pintype "passive"))
      (node (ref "C19") (pin "1") (pinfunction "1_1") (pintype "passive"))
      (node (ref "D1") (pin "C") (pinfunction "C_C") (pintype "passive"))
      (node (ref "ICSP1") (pin "2") (pinfunction "2_2") (pintype "passive"))
      (node (ref "JV1") (pin "1") (pinfunction "1_1") (pintype "passive"))
      (node (ref "L3") (pin "1") (pinfunction "1_1") (pintype "passive"))
      (node (ref "R1") (pin "2") (pinfunction "2_2") (pintype "passive"))
      (node (ref "R2") (pin "1") (pinfunction "1_1") (pintype "passive"))
      (node (ref "R5") (pin "2") (pinfunction "2_2") (pintype "passive"))
      (node (ref "SV5") (pin "9") (pinfunction "9_9") (pintype "passive"))
      (node (ref "SV6") (pin "11") (pinfunction "11_11") (pintype "passive"))
    )
    (net (code "2") (name "+12V") (class "Default")
      (node (ref "1R31") (pin "2") (pinfunction "2_2") (pintype "passive"))
      (node (ref "1VT5") (pin "E") (pinfunction "E_E") (pintype "passive"))
      (node (ref "3C10") (pin "2") (pinfunction "2_2") (pintype "passive"))
      (node (ref "3C9") (pin "+") (pinfunction "+_+") (pintype "passive"))
      (node (ref "3R7") (pin "2") (pinfunction "2_2") (pintype "passive"))
      (node (ref "3VD2") (pin "C") (pinfunction "C_C") (pintype "passive"))
    )
    (net (code "3") (name "/AGND") (class "Default")
      (node (ref "4D1") (pin "43") (pinfunction "GND3_43") (pintype "power_in"))
    )
    (net (code "4") (name "/AREF") (class "Default")
      (node (ref "4D1") (pin "42") (pinfunction "AREF_42") (pintype "power_in"))
      (node (ref "C1") (pin "2") (pinfunction "2_2") (pintype "passive"))
    )
    (net (code "5") (name "/AVCC") (class "Default")
      (node (ref "4D1") (pin "24") (pinfunction "AVCC_24") (pintype "power_in"))
      (node (ref "4D1") (pin "44") (pinfunction "AVCC1_44") (pintype "power_in"))
      (node (ref "C17") (pin "1") (pinfunction "1_1") (pintype "passive"))
      (node (ref "L3") (pin "2") (pinfunction "2_2") (pintype "passive"))
    )
    (net (code "6") (name "/CD1") (class "Default")
      (node (ref "SV5") (pin "8") (pinfunction "8_8") (pintype "passive"))
    )
    (net (code "7") (name "/CD2") (class "Default")
      (node (ref "SV5") (pin "7") (pinfunction "7_7") (pintype "passive"))
      (node (ref "SV6") (pin "9") (pinfunction "9_9") (pintype "passive"))
    )
    (net (code "8") (name "/CD3") (class "Default")
      (node (ref "SV5") (pin "6") (pinfunction "6_6") (pintype "passive"))
    )
    (net (code "9") (name "/CR+") (class "Default")
      (node (ref "1D1") (pin "5") (pinfunction "DP4_5") (pintype "bidirectional"))
      (node (ref "PINS") (pin "2") (pinfunction "2_2") (pintype "passive"))
    )
    (net (code "10") (name "/CR-") (class "Default")
      (node (ref "1D1") (pin "4") (pinfunction "DM4_4") (pintype "bidirectional"))
      (node (ref "PINS") (pin "1") (pinfunction "1_1") (pintype "passive"))
    )
    (net (code "11") (name "/D+") (class "Default")
      (node (ref "1R2") (pin "2") (pinfunction "2_2") (pintype "passive"))
      (node (ref "J_U1") (pin "2") (pinfunction "2_2") (pintype "passive"))
      (node (ref "RN") (pin "7") (pinfunction "2_7") (pintype "passive"))
      (node (ref "RU1") (pin "1") (pinfunction "1_1") (pintype "passive"))
      (node (ref "U_U3") (pin "1") (pinfunction "1_1") (pintype "passive"))
    )
    (net (code "12") (name "/D-") (class "Default")
      (node (ref "1R1") (pin "2") (pinfunction "2_2") (pintype "passive"))
      (node (ref "J_U2") (pin "1") (pinfunction "P$1_1") (pintype "bidirectional"))
      (node (ref "RN") (pin "8") (pinfunction "2_8") (pintype "passive"))
      (node (ref "RU2") (pin "1") (pinfunction "1_1") (pintype "passive"))
      (node (ref "U_U4") (pin "1") (pinfunction "1_1") (pintype "passive"))
    )
    (net (code "13") (name "/D0") (class "Default")
      (node (ref "5D1") (pin "40") (pinfunction "(T0/XCK)PB0_40") (pintype "bidirectional"))
    )
    (net (code "14") (name "/D1") (class "Default")
      (node (ref "5D1") (pin "41") (pinfunction "(T1)PB1_41") (pintype "bidirectional"))
    )
    (net (code "15") (name "/D2") (class "Default")
      (node (ref "5D1") (pin "42") (pinfunction "(AIN0/INT2)PB2_42") (pintype "bidirectional"))
    )
    (net (code "16") (name "/D3") (class "Default")
      (node (ref "5D1") (pin "43") (pinfunction "(AIN1/OC0)PB3_43") (pintype "bidirectional"))
    )
    (net (code "17") (name "/D4") (class "Default")
      (node (ref "5D1") (pin "44") (pinfunction "(SS)PB4_44") (pintype "bidirectional"))
    )
    (net (code "18") (name "/DMI") (class "Default")
      (node (ref "1D1") (pin "15") (pinfunction "DMU_15") (pintype "bidirectional"))
      (node (ref "RN") (pin "1") (pinfunction "1_1") (pintype "passive"))
    )
    (net (code "19") (name "/DPI") (class "Default")
      (node (ref "1D1") (pin "16") (pinfunction "DPU_16") (pintype "bidirectional"))
      (node (ref "RN") (pin "2") (pinfunction "1_2") (pintype "passive"))
    )
    (net (code "20") (name "/HWB") (class "Default")
      (node (ref "4D1") (pin "33") (pinfunction "(#HWB)PE2_33") (pintype "bidirectional"))
      (node (ref "R5") (pin "1") (pinfunction "1_1") (pintype "passive"))
    )
    (net (code "21") (name "/KBB1") (class "Default")
      (node (ref "SV6") (pin "2") (pinfunction "2_2") (pintype "passive"))
    )
    (net (code "22") (name "/KBB2") (class "Default")
      (node (ref "SV6") (pin "3") (pinfunction "3_3") (pintype "passive"))
    )
    (net (code "23") (name "/KBB3") (class "Default")
      (node (ref "SV6") (pin "4") (pinfunction "4_4") (pintype "passive"))
    )
    (net (code "24") (name "/KBB4") (class "Default")
      (node (ref "SV6") (pin "5") (pinfunction "5_5") (pintype "passive"))
    )
    (net (code "25") (name "/KBB5") (class "Default")
      (node (ref "SV6") (pin "6") (pinfunction "6_6") (pintype "passive"))
    )
    (net (code "26") (name "/KBB6") (class "Default")
      (node (ref "SV6") (pin "7") (pinfunction "7_7") (pintype "passive"))
    )
    (net (code "27") (name "/KBN1") (class "Default")
      (node (ref "SV5") (pin "2") (pinfunction "2_2") (pintype "passive"))
    )
    (net (code "28") (name "/KBN2") (class "Default")
      (node (ref "SV5") (pin "3") (pinfunction "3_3") (pintype "passive"))
    )
    (net (code "29") (name "/KBN3") (class "Default")
      (node (ref "SV5") (pin "5") (pinfunction "5_5") (pintype "passive"))
    )
    (net (code "30") (name "/LED_NUM") (class "Default")
      (node (ref "SV5") (pin "4") (pinfunction "4_4") (pintype "passive"))
    )
    (net (code "31") (name "/LED{slash}~{STK500}") (class "Default")
      (node (ref "1R13") (pin "1") (pinfunction "1_1") (pintype "passive"))
      (node (ref "5D5") (pin "8") (pinfunction "I0_8") (pintype "input"))
      (node (ref "5D5") (pin "9") (pinfunction "I1_9") (pintype "input"))
      (node (ref "5D6") (pin "1") (pinfunction "G_1") (pintype "input"))
      (node (ref "5D6") (pin "2") (pinfunction "A1_2") (pintype "input"))
      (node (ref "D2") (pin "A") (pinfunction "A_A") (pintype "passive"))
      (node (ref "D3") (pin "A") (pinfunction "A_A") (pintype "passive"))
    )
    (net (code "32") (name "/MISO8535") (class "Default")
      (node (ref "5D1") (pin "2") (pinfunction "(MISO)PB6_2") (pintype "bidirectional"))
      (node (ref "5D4") (pin "15") (pinfunction "A3_15") (pintype "input"))
      (node (ref "5D4") (pin "16") (pinfunction "Y2_16") (pintype "tri_state"))
      (node (ref "ISP1") (pin "1") (pinfunction "1_1") (pintype "passive"))
      (node (ref "JI") (pin "2") (pinfunction "2_2") (pintype "passive"))
    )
    (net (code "33") (name "/MOSI8535") (class "Default")
      (node (ref "5D1") (pin "1") (pinfunction "(MOSI)PB5_1") (pintype "bidirectional"))
      (node (ref "5D4") (pin "17") (pinfunction "A4_17") (pintype "input"))
      (node (ref "5D4") (pin "18") (pinfunction "Y1_18") (pintype "tri_state"))
      (node (ref "ISP1") (pin "4") (pinfunction "4_4") (pintype "passive"))
      (node (ref "JO") (pin "2") (pinfunction "2_2") (pintype "passive"))
    )
    (net (code "34") (name "/N$74") (class "Default")
      (node (ref "LEDS") (pin "6") (pinfunction "6_6") (pintype "passive"))
    )
    (net (code "35") (name "/PD2") (class "Default")
      (node (ref "1R28") (pin "1") (pinfunction "1_1") (pintype "passive"))
      (node (ref "5D1") (pin "11") (pinfunction "(INT0)PD2_11") (pintype "bidirectional"))
    )
    (net (code "36") (name "/PD5") (class "Default")
      (node (ref "4R9") (pin "1") (pinfunction "1_1") (pintype "passive"))
      (node (ref "5D1") (pin "14") (pinfunction "(OC1A)PD5_14") (pintype "bidirectional"))
    )
    (net (code "37") (name "/PD7") (class "Default")
      (node (ref "4VT6") (pin "3") (pinfunction "D_3") (pintype "passive"))
      (node (ref "5D1") (pin "16") (pinfunction "(OC2)PD7_16") (pintype "bidirectional"))
      (node (ref "JX1") (pin "1") (pinfunction "1_1") (pintype "passive"))
    )
    (net (code "38") (name "/PPC0(BS2)") (class "Default")
      (node (ref "5D1") (pin "19") (pinfunction "PC0(SCL)_19") (pintype "bidirectional"))
    )
    (net (code "39") (name "/PPC1(RB)") (class "Default")
      (node (ref "5D1") (pin "20") (pinfunction "PC1(SDA)_20") (pintype "bidirectional"))
    )
    (net (code "40") (name "/PPC2(~{OE})") (class "Default")
      (node (ref "5D1") (pin "21") (pinfunction "PC2_21") (pintype "bidirectional"))
      (node (ref "D7") (pin "A") (pinfunction "A_A") (pintype "passive"))
      (node (ref "D8") (pin "A") (pinfunction "A_A") (pintype "passive"))
    )
    (net (code "41") (name "/PPC3(WR)") (class "Default")
      (node (ref "5D1") (pin "22") (pinfunction "PC3_22") (pintype "bidirectional"))
    )
    (net (code "42") (name "/PPC4(BS1)") (class "Default")
      (node (ref "5D1") (pin "23") (pinfunction "PC4_23") (pintype "bidirectional"))
    )
    (net (code "43") (name "/PPC5(XA0)") (class "Default")
      (node (ref "5D1") (pin "24") (pinfunction "PC5_24") (pintype "bidirectional"))
    )
    (net (code "44") (name "/PPC6(XA1)") (class "Default")
      (node (ref "5D1") (pin "25") (pinfunction "(TOSC1)PC6_25") (pintype "bidirectional"))
    )
    (net (code "45") (name "/PPC7(PAGEL)") (class "Default")
      (node (ref "5D1") (pin "26") (pinfunction "(TOSC2)PC7_26") (pintype "bidirectional"))
    )
    (net (code "46") (name "/RD+") (class "Default")
      (node (ref "1D1") (pin "11") (pinfunction "DP1_11") (pintype "bidirectional"))
      (node (ref "J_U1") (pin "1") (pinfunction "1_1") (pintype "passive"))
      (node (ref "U_U2") (pin "1") (pinfunction "1_1") (pintype "passive"))
    )
    (net (code "47") (name "/RD-") (class "Default")
      (node (ref "1D1") (pin "10") (pinfunction "DM1_10") (pintype "bidirectional"))
      (node (ref "J_U2") (pin "2") (pinfunction "P$2_2") (pintype "bidirectional"))
      (node (ref "U_U1") (pin "1") (pinfunction "1_1") (pintype "passive"))
    )
    (net (code "48") (name "/RESET(P)") (class "Default")
      (node (ref "ISP1") (pin "5") (pinfunction "5_5") (pintype "passive"))
      (node (ref "JP1") (pin "2") (pinfunction "2_2") (pintype "passive"))
      (node (ref "RES1") (pin "2") (pinfunction "2_2") (pintype "passive"))
    )
    (net (code "49") (name "/RESET8535") (class "Default")
      (node (ref "1C22") (pin "2") (pinfunction "2_2") (pintype "passive"))
      (node (ref "1R41") (pin "1") (pinfunction "1_1") (pintype "passive"))
      (node (ref "5D1") (pin "4") (pinfunction "RESET_4") (pintype "input"))
      (node (ref "JP1") (pin "1") (pinfunction "1_1") (pintype "passive"))
      (node (ref "JR") (pin "2") (pinfunction "2_2") (pintype "passive"))
      (node (ref "P_RESET") (pin "2") (pinfunction "2_2") (pintype "passive"))
      (node (ref "RES1") (pin "3") (pinfunction "3_3") (pintype "passive"))
    )
    (net (code "50") (name "/RX_LED") (class "Default")
      (node (ref "5D6") (pin "11") (pinfunction "A1_11") (pintype "input"))
      (node (ref "RXTXLED") (pin "3") (pinfunction "3_3") (pintype "passive"))
    )
    (net (code "51") (name "/RX_STK500") (class "Default")
      (node (ref "5D1") (pin "10") (pinfunction "(TXD)PD1_10") (pintype "bidirectional"))
      (node (ref "JRX") (pin "1") (pinfunction "1_1") (pintype "passive"))
    )
    (net (code "52") (name "/RX_USB") (class "Default")
      (node (ref "2D1") (pin "5") (pinfunction "RXD_5") (pintype "bidirectional"))
      (node (ref "5D6") (pin "12") (pinfunction "Y4_12") (pintype "tri_state"))
      (node (ref "5D6") (pin "9") (pinfunction "Y1_9") (pintype "tri_state"))
    )
    (net (code "53") (name "/SCK8535") (class "Default")
      (node (ref "5D1") (pin "3") (pinfunction "(SCK)PB7_3") (pintype "bidirectional"))
      (node (ref "5D4") (pin "11") (pinfunction "A1_11") (pintype "input"))
      (node (ref "5D4") (pin "12") (pinfunction "Y4_12") (pintype "tri_state"))
      (node (ref "5D4") (pin "13") (pinfunction "A2_13") (pintype "input"))
      (node (ref "ISP1") (pin "3") (pinfunction "3_3") (pintype "passive"))
      (node (ref "JS") (pin "2") (pinfunction "2_2") (pintype "passive"))
    )
    (net (code "54") (name "/SWCLK(XTAL1)") (class "Default")
      (node (ref "4VT6") (pin "2") (pinfunction "S_2") (pintype "passive"))
      (node (ref "JX1") (pin "2") (pinfunction "2_2") (pintype "passive"))
    )
    (net (code "55") (name "/TRST(RESET)") (class "Default")
      (node (ref "1R32") (pin "1") (pinfunction "1_1") (pintype "passive"))
      (node (ref "1VT6") (pin "3") (pinfunction "C_3") (pintype "passive"))
      (node (ref "JP1") (pin "3") (pinfunction "3_3") (pintype "passive"))
      (node (ref "RES1") (pin "1") (pinfunction "1_1") (pintype "passive"))
    )
    (net (code "56") (name "/TX_LED") (class "Default")
      (node (ref "5D6") (pin "3") (pinfunction "Y4_3") (pintype "tri_state"))
      (node (ref "RXTXLED") (pin "1") (pinfunction "1_1") (pintype "passive"))
    )
    (net (code "57") (name "/TX_STK500") (class "Default")
      (node (ref "5D1") (pin "9") (pinfunction "(RXD)PD0_9") (pintype "bidirectional"))
      (node (ref "JTX") (pin "2") (pinfunction "2_2") (pintype "passive"))
    )
    (net (code "58") (name "/TX_USB") (class "Default")
      (node (ref "2D1") (pin "1") (pinfunction "TXD_1") (pintype "bidirectional"))
      (node (ref "5D6") (pin "17") (pinfunction "A4_17") (pintype "input"))
      (node (ref "5D6") (pin "4") (pinfunction "A2_4") (pintype "input"))
      (node (ref "JR") (pin "1") (pinfunction "1_1") (pintype "passive"))
    )
    (net (code "59") (name "/UCAP") (class "Default")
      (node (ref "4D1") (pin "6") (pinfunction "UCAP_6") (pintype "passive"))
      (node (ref "C2") (pin "1") (pinfunction "1_1") (pintype "passive"))
    )
    (net (code "60") (name "/UGND") (class "Default")
      (node (ref "4D1") (pin "5") (pinfunction "UGND_5") (pintype "power_in"))
      (node (ref "C2") (pin "2") (pinfunction "2_2") (pintype "passive"))
      (node (ref "L1") (pin "1") (pinfunction "1_1") (pintype "passive"))
    )
    (net (code "61") (name "/UMISO(D1)") (class "Default")
      (node (ref "4D1") (pin "11") (pinfunction "(PD0/MISO/PCINT3)PB3_11") (pintype "bidirectional"))
      (node (ref "DATA3") (pin "1") (pinfunction "1_1") (pintype "passive"))
      (node (ref "ICSP1") (pin "1") (pinfunction "1_1") (pintype "passive"))
    )
    (net (code "62") (name "/UMOSI(D2)") (class "Default")
      (node (ref "4D1") (pin "10") (pinfunction "(PDI/MOSI/PCINT2)PB2_10") (pintype "bidirectional"))
      (node (ref "DATA2") (pin "1") (pinfunction "1_1") (pintype "passive"))
      (node (ref "ICSP1") (pin "4") (pinfunction "4_4") (pintype "passive"))
    )
    (net (code "63") (name "/UPB0") (class "Default")
      (node (ref "4D1") (pin "8") (pinfunction "(SS/PCINT0)PB0_8") (pintype "bidirectional"))
      (node (ref "DATA0") (pin "1") (pinfunction "1_1") (pintype "passive"))
    )
    (net (code "64") (name "/UPB4") (class "Default")
      (node (ref "4D1") (pin "28") (pinfunction "(ADC11/PCINT4)PB4_28") (pintype "bidirectional"))
      (node (ref "DATA4") (pin "1") (pinfunction "1_1") (pintype "passive"))
      (node (ref "LEDS") (pin "2") (pinfunction "2_2") (pintype "passive"))
    )
    (net (code "65") (name "/UPB5") (class "Default")
      (node (ref "4D1") (pin "29") (pinfunction "(PCINT5/OC1A/#OC4B/ADC12)PB5_29") (pintype "bidirectional"))
      (node (ref "5D4") (pin "2") (pinfunction "A1_2") (pintype "input"))
      (node (ref "5D4") (pin "3") (pinfunction "Y4_3") (pintype "tri_state"))
      (node (ref "DATA5") (pin "1") (pinfunction "1_1") (pintype "passive"))
      (node (ref "LEDS") (pin "5") (pinfunction "5_5") (pintype "passive"))
    )
    (net (code "66") (name "/UPB6") (class "Default")
      (node (ref "4D1") (pin "30") (pinfunction "(PCINT6/OC1B/OC4B/ADC13)PB6_30") (pintype "bidirectional"))
      (node (ref "5D4") (pin "4") (pinfunction "A2_4") (pintype "input"))
      (node (ref "5D4") (pin "5") (pinfunction "Y3_5") (pintype "tri_state"))
      (node (ref "DATA6") (pin "1") (pinfunction "1_1") (pintype "passive"))
      (node (ref "LEDS") (pin "3") (pinfunction "3_3") (pintype "passive"))
    )
    (net (code "67") (name "/UPB7") (class "Default")
      (node (ref "4D1") (pin "12") (pinfunction "(PCINT7/OC0A/OC1C/#RTS)PB7_12") (pintype "bidirectional"))
      (node (ref "5D4") (pin "8") (pinfunction "A4_8") (pintype "input"))
      (node (ref "5D4") (pin "9") (pinfunction "Y1_9") (pintype "tri_state"))
      (node (ref "DATA7") (pin "1") (pinfunction "1_1") (pintype "passive"))
      (node (ref "LEDS") (pin "1") (pinfunction "1_1") (pintype "passive"))
    )
    (net (code "68") (name "/UPC6") (class "Default")
      (node (ref "4D1") (pin "31") (pinfunction "(OC3A/#0C4A)PC6_31") (pintype "bidirectional"))
      (node (ref "R6") (pin "1") (pinfunction "1_1") (pintype "passive"))
    )
    (net (code "69") (name "/UPC7") (class "Default")
      (node (ref "4D1") (pin "32") (pinfunction "(ICP3/CLK0/OC4A)PC7_32") (pintype "bidirectional"))
      (node (ref "LEDS") (pin "4") (pinfunction "4_4") (pintype "passive"))
      (node (ref "R4") (pin "1") (pinfunction "1_1") (pintype "passive"))
    )
    (net (code "70") (name "/UPD0") (class "Default")
      (node (ref "4D1") (pin "18") (pinfunction "(OC0B/SCL/INT0)PD0_18") (pintype "bidirectional"))
      (node (ref "R15") (pin "1") (pinfunction "1_1") (pintype "passive"))
    )
    (net (code "71") (name "/UPD1") (class "Default")
      (node (ref "4D1") (pin "19") (pinfunction "(SDA/INT1)PD1_19") (pintype "bidirectional"))
      (node (ref "R/!B") (pin "1") (pinfunction "1_1") (pintype "passive"))
      (node (ref "R13") (pin "1") (pinfunction "1_1") (pintype "passive"))
    )
    (net (code "72") (name "/UPD3") (class "Default")
      (node (ref "!WR") (pin "1") (pinfunction "1_1") (pintype "passive"))
      (node (ref "4D1") (pin "21") (pinfunction "(TXD1/INT3)PD3_21") (pintype "bidirectional"))
      (node (ref "R11") (pin "1") (pinfunction "1_1") (pintype "passive"))
    )
    (net (code "73") (name "/UPD4") (class "Default")
      (node (ref "4D1") (pin "25") (pinfunction "(ICP1/ADC8)PD4_25") (pintype "bidirectional"))
      (node (ref "BS1") (pin "1") (pinfunction "1_1") (pintype "passive"))
      (node (ref "R10") (pin "1") (pinfunction "1_1") (pintype "passive"))
    )
    (net (code "74") (name "/UPD5") (class "Default")
      (node (ref "4D1") (pin "22") (pinfunction "(XCK1/#CTS)PD5_22") (pintype "bidirectional"))
      (node (ref "R9") (pin "1") (pinfunction "1_1") (pintype "passive"))
      (node (ref "XA0") (pin "1") (pinfunction "1_1") (pintype "passive"))
    )
    (net (code "75") (name "/UPD6") (class "Default")
      (node (ref "4D1") (pin "26") (pinfunction "(T1/#OC4D/ADC9)PD6_26") (pintype "bidirectional"))
      (node (ref "R8") (pin "1") (pinfunction "1_1") (pintype "passive"))
      (node (ref "XA1") (pin "1") (pinfunction "1_1") (pintype "passive"))
    )
    (net (code "76") (name "/UPD7") (class "Default")
      (node (ref "4D1") (pin "27") (pinfunction "(T0/OC4D/ADC10)PD7_27") (pintype "bidirectional"))
      (node (ref "PAG") (pin "1") (pinfunction "1_1") (pintype "passive"))
      (node (ref "R7") (pin "1") (pinfunction "1_1") (pintype "passive"))
    )
    (net (code "77") (name "/UPE6") (class "Default")
      (node (ref "4D1") (pin "1") (pinfunction "(INT6/AIN0)PE6_1") (pintype "bidirectional"))
      (node (ref "BS2") (pin "1") (pinfunction "1_1") (pintype "passive"))
    )
    (net (code "78") (name "/UPF0") (class "Default")
      (node (ref "4D1") (pin "41") (pinfunction "(ADC0)PF0_41") (pintype "bidirectional"))
      (node (ref "R21") (pin "1") (pinfunction "1_1") (pintype "passive"))
    )
    (net (code "79") (name "/UPF1") (class "Default")
      (node (ref "4D1") (pin "40") (pinfunction "(ADC1)PF1_40") (pintype "bidirectional"))
      (node (ref "R20") (pin "1") (pinfunction "1_1") (pintype "passive"))
    )
    (net (code "80") (name "/UPF4") (class "Default")
      (node (ref "4D1") (pin "39") (pinfunction "(ADC4/TCK)PF4_39") (pintype "bidirectional"))
      (node (ref "R19") (pin "1") (pinfunction "1_1") (pintype "passive"))
    )
    (net (code "81") (name "/UPF5") (class "Default")
      (node (ref "4D1") (pin "38") (pinfunction "(ADC5/TMS)PF5_38") (pintype "bidirectional"))
      (node (ref "R18") (pin "1") (pinfunction "1_1") (pintype "passive"))
    )
    (net (code "82") (name "/UPF6") (class "Default")
      (node (ref "4D1") (pin "37") (pinfunction "(ADC6/TDO)PF6_37") (pintype "bidirectional"))
      (node (ref "R17") (pin "1") (pinfunction "1_1") (pintype "passive"))
    )
    (net (code "83") (name "/UPF7") (class "Default")
      (node (ref "4D1") (pin "36") (pinfunction "(ADC7/TDI)PF7_36") (pintype "bidirectional"))
      (node (ref "R16") (pin "1") (pinfunction "1_1") (pintype "passive"))
    )
    (net (code "84") (name "/URESET") (class "Default")
      (node (ref "4D1") (pin "13") (pinfunction "RESET_13") (pintype "input"))
      (node (ref "D1") (pin "A") (pinfunction "A_A") (pintype "passive"))
      (node (ref "ICSP1") (pin "5") (pinfunction "5_5") (pintype "passive"))
      (node (ref "R1") (pin "1") (pinfunction "1_1") (pintype "passive"))
      (node (ref "RES") (pin "1") (pinfunction "1_1") (pintype "passive"))
      (node (ref "RESET") (pin "C") (pinfunction "C_C") (pintype "passive"))
      (node (ref "RESET1") (pin "1") (pinfunction "1_1") (pintype "passive"))
      (node (ref "RESET1") (pin "2") (pinfunction "2_2") (pintype "passive"))
      (node (ref "RESET1") (pin "5") (pinfunction "5-GND_5") (pintype "power_in"))
    )
    (net (code "85") (name "/USCK(D3)") (class "Default")
      (node (ref "4D1") (pin "9") (pinfunction "(SCLK/PCINT1)PB1_9") (pintype "bidirectional"))
      (node (ref "DATA1") (pin "1") (pinfunction "1_1") (pintype "passive"))
      (node (ref "ICSP1") (pin "3") (pinfunction "3_3") (pintype "passive"))
    )
    (net (code "86") (name "/UU+") (class "Default")
      (node (ref "1D1") (pin "7") (pinfunction "DP3_7") (pintype "bidirectional"))
      (node (ref "2R4") (pin "2") (pinfunction "2_2") (pintype "passive"))
      (node (ref "2R8") (pin "1") (pinfunction "1_1") (pintype "passive"))
    )
    (net (code "87") (name "/UU-") (class "Default")
      (node (ref "1D1") (pin "6") (pinfunction "DM3_6") (pintype "bidirectional"))
      (node (ref "2R1") (pin "1") (pinfunction "1_1") (pintype "passive"))
    )
    (net (code "88") (name "/VD1V8") (class "Default")
      (node (ref "1C3") (pin "1") (pinfunction "1_1") (pintype "passive"))
      (node (ref "1C4") (pin "1") (pinfunction "1_1") (pintype "passive"))
      (node (ref "1D1") (pin "12") (pinfunction "VD18_O_12") (pintype "bidirectional"))
      (node (ref "1D1") (pin "28") (pinfunction "VD18_28") (pintype "bidirectional"))
    )
    (net (code "89") (name "/VD3V3") (class "Default")
      (node (ref "1C5") (pin "1") (pinfunction "1_1") (pintype "passive"))
      (node (ref "1C6") (pin "1") (pinfunction "1_1") (pintype "passive"))
      (node (ref "1D1") (pin "13") (pinfunction "VD33_13") (pintype "bidirectional"))
      (node (ref "1D1") (pin "21") (pinfunction "VD33_O_21") (pintype "bidirectional"))
      (node (ref "1R3") (pin "1") (pinfunction "1_1") (pintype "passive"))
      (node (ref "1R4") (pin "1") (pinfunction "1_1") (pintype "passive"))
      (node (ref "1R5") (pin "1") (pinfunction "1_1") (pintype "passive"))
    )
    (net (code "90") (name "/VTG") (class "Default")
      (node (ref "4R10") (pin "1") (pinfunction "1_1") (pintype "passive"))
      (node (ref "4VT5") (pin "3") (pinfunction "D_3") (pintype "passive"))
      (node (ref "ISP1") (pin "2") (pinfunction "2_2") (pintype "passive"))
      (node (ref "JV1") (pin "2") (pinfunction "2_2") (pintype "passive"))
    )
    (net (code "91") (name "/VUSBH") (class "Default")
      (node (ref "1C10") (pin "1") (pinfunction "1_1") (pintype "passive"))
      (node (ref "1X2") (pin "1") (pinfunction "1_1") (pintype "passive"))
      (node (ref "F2") (pin "1") (pinfunction "1_1") (pintype "passive"))
      (node (ref "F2") (pin "2") (pinfunction "2_2") (pintype "passive"))
    )
    (net (code "92") (name "/XTAL1") (class "Default")
      (node (ref "4D1") (pin "17") (pinfunction "XTAL1_17") (pintype "bidirectional"))
      (node (ref "C20") (pin "2") (pinfunction "2_2") (pintype "passive"))
      (node (ref "R100") (pin "2") (pinfunction "2_2") (pintype "passive"))
      (node (ref "XTAL1") (pin "1") (pinfunction "1_1") (pintype "passive"))
      (node (ref "Z1") (pin "3") (pinfunction "C2_3") (pintype "passive"))
      (node (ref "Z1A") (pin "2") (pinfunction "2_2") (pintype "passive"))
    )
    (net (code "93") (name "/XTAL2") (class "Default")
      (node (ref "4D1") (pin "16") (pinfunction "XTAL2_16") (pintype "bidirectional"))
      (node (ref "C24") (pin "1") (pinfunction "1_1") (pintype "passive"))
      (node (ref "R100") (pin "1") (pinfunction "1_1") (pintype "passive"))
      (node (ref "Z1") (pin "1") (pinfunction "C1_1") (pintype "passive"))
      (node (ref "Z1A") (pin "1") (pinfunction "1_1") (pintype "passive"))
    )
    (net (code "94") (name "/~{HVPP_EN}") (class "Default")
      (node (ref "1R16") (pin "1") (pinfunction "1_1") (pintype "passive"))
      (node (ref "5D5") (pin "2") (pinfunction "I1_2") (pintype "input"))
      (node (ref "D3") (pin "C") (pinfunction "C_C") (pintype "passive"))
      (node (ref "D9") (pin "A") (pinfunction "A_A") (pintype "passive"))
      (node (ref "JP") (pin "3") (pinfunction "3_3") (pintype "passive"))
    )
    (net (code "95") (name "/~{ISP_EN}") (class "Default")
      (node (ref "1R15") (pin "1") (pinfunction "1_1") (pintype "passive"))
      (node (ref "5D5") (pin "1") (pinfunction "I0_1") (pintype "input"))
      (node (ref "D2") (pin "C") (pinfunction "C_C") (pintype "passive"))
      (node (ref "D6") (pin "A") (pinfunction "A_A") (pintype "passive"))
      (node (ref "JP") (pin "1") (pinfunction "1_1") (pintype "passive"))
    )
    (net (code "96") (name "/~{OE}(UPD2)") (class "Default")
      (node (ref "!OE") (pin "1") (pinfunction "1_1") (pintype "passive"))
      (node (ref "4D1") (pin "20") (pinfunction "(RXD1/AIN1/INT2)PD2_20") (pintype "bidirectional"))
      (node (ref "R12") (pin "1") (pinfunction "1_1") (pintype "passive"))
    )
    (net (code "97") (name "3x2M_NM") (class "Default")
      (node (ref "1C1") (pin "1") (pinfunction "1_1") (pintype "passive"))
      (node (ref "1C10") (pin "2") (pinfunction "2_2") (pintype "passive"))
      (node (ref "1C19") (pin "2") (pinfunction "2_2") (pintype "passive"))
      (node (ref "1C2") (pin "1") (pinfunction "1_1") (pintype "passive"))
      (node (ref "1C20") (pin "1") (pinfunction "1_1") (pintype "passive"))
      (node (ref "1C21") (pin "1") (pinfunction "1_1") (pintype "passive"))
      (node (ref "1C22") (pin "1") (pinfunction "1_1") (pintype "passive"))
      (node (ref "1C23") (pin "1") (pinfunction "1_1") (pintype "passive"))
      (node (ref "1C24") (pin "1") (pinfunction "1_1") (pintype "passive"))
      (node (ref "1C3") (pin "2") (pinfunction "2_2") (pintype "passive"))
      (node (ref "1C4") (pin "2") (pinfunction "2_2") (pintype "passive"))
      (node (ref "1C5") (pin "2") (pinfunction "2_2") (pintype "passive"))
      (node (ref "1C6") (pin "2") (pinfunction "2_2") (pintype "passive"))
      (node (ref "1C7") (pin "-") (pinfunction "-_-") (pintype "passive"))
      (node (ref "1C8") (pin "1") (pinfunction "1_1") (pintype "passive"))
      (node (ref "1C9") (pin "1") (pinfunction "1_1") (pintype "passive"))
      (node (ref "1D1") (pin "1") (pinfunction "VSS_1") (pintype "bidirectional"))
      (node (ref "1R14") (pin "1") (pinfunction "1_1") (pintype "passive"))
      (node (ref "1R17") (pin "1") (pinfunction "1_1") (pintype "passive"))
      (node (ref "1R36") (pin "1") (pinfunction "1_1") (pintype "passive"))
      (node (ref "1R38") (pin "1") (pinfunction "1_1") (pintype "passive"))
      (node (ref "1R42") (pin "1") (pinfunction "1_1") (pintype "passive"))
      (node (ref "1R7") (pin "1") (pinfunction "1_1") (pintype "passive"))
      (node (ref "1R8") (pin "1") (pinfunction "1_1") (pintype "passive"))
      (node (ref "1RJ") (pin "2") (pinfunction "2_2") (pintype "passive"))
      (node (ref "1VT4") (pin "2") (pinfunction "E_2") (pintype "passive"))
      (node (ref "1VT6") (pin "2") (pinfunction "E_2") (pintype "passive"))
      (node (ref "1X1") (pin "4") (pinfunction "4_4") (pintype "passive"))
      (node (ref "1X1") (pin "S1") (pinfunction "S1_S1") (pintype "passive"))
      (node (ref "1X1") (pin "S2") (pinfunction "S2_S2") (pintype "passive"))
      (node (ref "1X2") (pin "4") (pinfunction "4_4") (pintype "passive"))
      (node (ref "2C1") (pin "1") (pinfunction "1_1") (pintype "passive"))
      (node (ref "2C2") (pin "1") (pinfunction "1_1") (pintype "passive"))
      (node (ref "2C3") (pin "2") (pinfunction "2_2") (pintype "passive"))
      (node (ref "2C4") (pin "1") (pinfunction "1_1") (pintype "passive"))
      (node (ref "2C5") (pin "1") (pinfunction "1_1") (pintype "passive"))
      (node (ref "2D1") (pin "18") (pinfunction "GND_18") (pintype "bidirectional"))
      (node (ref "2D1") (pin "21") (pinfunction "GND_21") (pintype "bidirectional"))
      (node (ref "2D1") (pin "25") (pinfunction "GND_A_25") (pintype "bidirectional"))
      (node (ref "2D1") (pin "26") (pinfunction "PLL_TEST_26") (pintype "bidirectional"))
      (node (ref "2D1") (pin "7") (pinfunction "GND_7") (pintype "bidirectional"))
      (node (ref "2D2") (pin "1") (pinfunction "A0_1") (pintype "input"))
      (node (ref "2D2") (pin "2") (pinfunction "A1_2") (pintype "input"))
      (node (ref "2D2") (pin "3") (pinfunction "A2_3") (pintype "input"))
      (node (ref "2D2") (pin "4") (pinfunction "GND_4") (pintype "power_in"))
      (node (ref "2R2") (pin "1") (pinfunction "1_1") (pintype "passive"))
      (node (ref "3C10") (pin "1") (pinfunction "1_1") (pintype "passive"))
      (node (ref "3C6") (pin "2") (pinfunction "2_2") (pintype "passive"))
      (node (ref "3C7") (pin "2") (pinfunction "2_2") (pintype "passive"))
      (node (ref "3C8") (pin "-") (pinfunction "-_-") (pintype "passive"))
      (node (ref "3C9") (pin "-") (pinfunction "-_-") (pintype "passive"))
      (node (ref "3R8") (pin "1") (pinfunction "1_1") (pintype "passive"))
      (node (ref "4C2") (pin "1") (pinfunction "1_1") (pintype "passive"))
      (node (ref "4D1") (pin "15") (pinfunction "GND_15") (pintype "power_in"))
      (node (ref "4D1") (pin "23") (pinfunction "GND1_23") (pintype "power_in"))
      (node (ref "4D1") (pin "35") (pinfunction "GND2_35") (pintype "power_in"))
      (node (ref "4D1") (pin "P$1") (pinfunction "PAD_P$1") (pintype "power_in"))
      (node (ref "4R7") (pin "1") (pinfunction "1_1") (pintype "passive"))
      (node (ref "4VT4") (pin "2") (pinfunction "E_2") (pintype "passive"))
      (node (ref "5D1") (pin "18") (pinfunction "GND1_18") (pintype "power_in"))
      (node (ref "5D1") (pin "28") (pinfunction "GND_28") (pintype "power_in"))
      (node (ref "5D1") (pin "39") (pinfunction "GND2_39") (pintype "power_in"))
      (node (ref "5D1") (pin "6") (pinfunction "GND_6") (pintype "power_in"))
      (node (ref "5D2") (pin "10") (pinfunction "SER_10") (pintype "input"))
      (node (ref "5D2") (pin "15") (pinfunction "INH_15") (pintype "input"))
      (node (ref "5D2") (pin "8") (pinfunction "GND_8") (pintype "power_in"))
      (node (ref "5D3") (pin "2") (pinfunction "SWE_2") (pintype "passive"))
      (node (ref "5D3") (pin "4") (pinfunction "GND_4") (pintype "passive"))
      (node (ref "5D4") (pin "10") (pinfunction "GND_10") (pintype "power_in"))
      (node (ref "5D5") (pin "7") (pinfunction "VSS_7") (pintype "power_in"))
      (node (ref "5D6") (pin "10") (pinfunction "GND_10") (pintype "power_in"))
      (node (ref "C1") (pin "1") (pinfunction "1_1") (pintype "passive"))
      (node (ref "C17") (pin "2") (pinfunction "2_2") (pintype "passive"))
      (node (ref "C18") (pin "2") (pinfunction "2_2") (pintype "passive"))
      (node (ref "C19") (pin "2") (pinfunction "2_2") (pintype "passive"))
      (node (ref "C20") (pin "1") (pinfunction "1_1") (pintype "passive"))
      (node (ref "C24") (pin "2") (pinfunction "2_2") (pintype "passive"))
      (node (ref "ICSP1") (pin "6") (pinfunction "6_6") (pintype "passive"))
      (node (ref "ISP1") (pin "6") (pinfunction "6_6") (pintype "passive"))
      (node (ref "JP") (pin "2") (pinfunction "2_2") (pintype "passive"))
      (node (ref "JWP") (pin "1") (pinfunction "1_1") (pintype "passive"))
      (node (ref "L1") (pin "2") (pinfunction "2_2") (pintype "passive"))
      (node (ref "P_RESET") (pin "1") (pinfunction "1_1") (pintype "passive"))
      (node (ref "R10") (pin "2") (pinfunction "2_2") (pintype "passive"))
      (node (ref "R11") (pin "2") (pinfunction "2_2") (pintype "passive"))
      (node (ref "R12") (pin "2") (pinfunction "2_2") (pintype "passive"))
      (node (ref "R13") (pin "2") (pinfunction "2_2") (pintype "passive"))
      (node (ref "R15") (pin "2") (pinfunction "2_2") (pintype "passive"))
      (node (ref "R16") (pin "2") (pinfunction "2_2") (pintype "passive"))
      (node (ref "R17") (pin "2") (pinfunction "2_2") (pintype "passive"))
      (node (ref "R18") (pin "2") (pinfunction "2_2") (pintype "passive"))
      (node (ref "R19") (pin "2") (pinfunction "2_2") (pintype "passive"))
      (node (ref "R20") (pin "2") (pinfunction "2_2") (pintype "passive"))
      (node (ref "R21") (pin "2") (pinfunction "2_2") (pintype "passive"))
      (node (ref "R4") (pin "2") (pinfunction "2_2") (pintype "passive"))
      (node (ref "R6") (pin "2") (pinfunction "2_2") (pintype "passive"))
      (node (ref "R7") (pin "2") (pinfunction "2_2") (pintype "passive"))
      (node (ref "R8") (pin "2") (pinfunction "2_2") (pintype "passive"))
      (node (ref "R9") (pin "2") (pinfunction "2_2") (pintype "passive"))
      (node (ref "RESET1") (pin "3") (pinfunction "3_3") (pintype "passive"))
      (node (ref "RESET1") (pin "4") (pinfunction "4_4") (pintype "passive"))
      (node (ref "RU1") (pin "2") (pinfunction "2_2") (pintype "passive"))
      (node (ref "RU2") (pin "2") (pinfunction "2_2") (pintype "passive"))
      (node (ref "RXTXLED") (pin "2") (pinfunction "2_2") (pintype "passive"))
      (node (ref "SV5") (pin "1") (pinfunction "1_1") (pintype "passive"))
      (node (ref "SV6") (pin "1") (pinfunction "1_1") (pintype "passive"))
      (node (ref "T_RESET") (pin "2") (pinfunction "2_2") (pintype "passive"))
      (node (ref "Z1") (pin "2") (pinfunction "GND_2") (pintype "passive"))
      (node (ref "Z1") (pin "4") (pinfunction "GND_4") (pintype "passive"))
    )
    (net (code "98") (name "Net-(1D1-BUSJ)") (class "Default")
      (node (ref "1D1") (pin "19") (pinfunction "BUSJ_19") (pintype "bidirectional"))
      (node (ref "1R4") (pin "2") (pinfunction "2_2") (pintype "passive"))
    )
    (net (code "99") (name "Net-(1D1-DM2)") (class "Default")
      (node (ref "1D1") (pin "8") (pinfunction "DM2_8") (pintype "bidirectional"))
      (node (ref "1R12") (pin "1") (pinfunction "1_1") (pintype "passive"))
    )
    (net (code "100") (name "Net-(1D1-DP2)") (class "Default")
      (node (ref "1D1") (pin "9") (pinfunction "DP2_9") (pintype "bidirectional"))
      (node (ref "1R11") (pin "1") (pinfunction "1_1") (pintype "passive"))
    )
    (net (code "101") (name "Net-(1D1-DRV)") (class "Default")
      (node (ref "1D1") (pin "22") (pinfunction "DRV_22") (pintype "bidirectional"))
      (node (ref "1R10") (pin "2") (pinfunction "2_2") (pintype "passive"))
      (node (ref "1R9") (pin "2") (pinfunction "2_2") (pintype "passive"))
    )
    (net (code "102") (name "Net-(1D1-LED1)") (class "Default")
      (node (ref "1D1") (pin "23") (pinfunction "LED1_23") (pintype "bidirectional"))
      (node (ref "HL1") (pin "C") (pinfunction "C_C") (pintype "passive"))
      (node (ref "HL3") (pin "A") (pinfunction "A_A") (pintype "passive"))
    )
    (net (code "103") (name "Net-(1D1-LED2)") (class "Default")
      (node (ref "1D1") (pin "24") (pinfunction "LED2_24") (pintype "bidirectional"))
      (node (ref "HL2") (pin "C") (pinfunction "C_C") (pintype "passive"))
      (node (ref "HL4") (pin "A") (pinfunction "A_A") (pintype "passive"))
    )
    (net (code "104") (name "Net-(1D1-OVCJ)") (class "Default")
      (node (ref "1D1") (pin "26") (pinfunction "OVCJ_26") (pintype "bidirectional"))
      (node (ref "1R3") (pin "2") (pinfunction "2_2") (pintype "passive"))
    )
    (net (code "105") (name "Net-(1D1-REXT)") (class "Default")
      (node (ref "1D1") (pin "14") (pinfunction "REXT_14") (pintype "bidirectional"))
      (node (ref "1R8") (pin "2") (pinfunction "2_2") (pintype "passive"))
    )
    (net (code "106") (name "Net-(1D1-TESTJ)") (class "Default")
      (node (ref "1D1") (pin "27") (pinfunction "TESTJ_27") (pintype "bidirectional"))
      (node (ref "1RJ") (pin "1") (pinfunction "1_1") (pintype "passive"))
    )
    (net (code "107") (name "Net-(1D1-VBUSM)") (class "Default")
      (node (ref "1D1") (pin "18") (pinfunction "VBUSM_18") (pintype "bidirectional"))
      (node (ref "1R6") (pin "1") (pinfunction "1_1") (pintype "passive"))
      (node (ref "1R7") (pin "2") (pinfunction "2_2") (pintype "passive"))
    )
    (net (code "108") (name "Net-(1D1-XIN)") (class "Default")
      (node (ref "1C2") (pin "2") (pinfunction "2_2") (pintype "passive"))
      (node (ref "1D1") (pin "3") (pinfunction "XIN_3") (pintype "bidirectional"))
      (node (ref "1Z1") (pin "2") (pinfunction "2_2") (pintype "passive"))
    )
    (net (code "109") (name "Net-(1D1-XOUT)") (class "Default")
      (node (ref "1C1") (pin "2") (pinfunction "2_2") (pintype "passive"))
      (node (ref "1D1") (pin "2") (pinfunction "XOUT_2") (pintype "bidirectional"))
      (node (ref "1Z1") (pin "1") (pinfunction "1_1") (pintype "passive"))
    )
    (net (code "110") (name "Net-(1D1-XRSTJ)") (class "Default")
      (node (ref "1D1") (pin "17") (pinfunction "XRSTJ_17") (pintype "bidirectional"))
      (node (ref "1R5") (pin "2") (pinfunction "2_2") (pintype "passive"))
    )
    (net (code "111") (name "Net-(1R1-Pad1)") (class "Default")
      (node (ref "1R1") (pin "1") (pinfunction "1_1") (pintype "passive"))
      (node (ref "1X1") (pin "2") (pinfunction "2_2") (pintype "passive"))
    )
    (net (code "112") (name "Net-(1R2-Pad1)") (class "Default")
      (node (ref "1R2") (pin "1") (pinfunction "1_1") (pintype "passive"))
      (node (ref "1X1") (pin "3") (pinfunction "3_3") (pintype "passive"))
    )
    (net (code "113") (name "Net-(1R9-Pad1)") (class "Default")
      (node (ref "1R9") (pin "1") (pinfunction "1_1") (pintype "passive"))
      (node (ref "HL1") (pin "A") (pinfunction "A_A") (pintype "passive"))
      (node (ref "HL3") (pin "C") (pinfunction "C_C") (pintype "passive"))
    )
    (net (code "114") (name "Net-(1R10-Pad1)") (class "Default")
      (node (ref "1R10") (pin "1") (pinfunction "1_1") (pintype "passive"))
      (node (ref "HL2") (pin "A") (pinfunction "A_A") (pintype "passive"))
      (node (ref "HL4") (pin "C") (pinfunction "C_C") (pintype "passive"))
    )
    (net (code "115") (name "Net-(1R11-Pad2)") (class "Default")
      (node (ref "1R11") (pin "2") (pinfunction "2_2") (pintype "passive"))
      (node (ref "1X2") (pin "3") (pinfunction "3_3") (pintype "passive"))
    )
    (net (code "116") (name "Net-(1R12-Pad2)") (class "Default")
      (node (ref "1R12") (pin "2") (pinfunction "2_2") (pintype "passive"))
      (node (ref "1X2") (pin "2") (pinfunction "2_2") (pintype "passive"))
    )
    (net (code "117") (name "Net-(1R29-Pad2)") (class "Default")
      (node (ref "1R29") (pin "2") (pinfunction "2_2") (pintype "passive"))
      (node (ref "1R42") (pin "2") (pinfunction "2_2") (pintype "passive"))
      (node (ref "HW1") (pin "2") (pinfunction "2_2") (pintype "passive"))
    )
    (net (code "118") (name "Net-(1R30-Pad2)") (class "Default")
      (node (ref "1R30") (pin "2") (pinfunction "2_2") (pintype "passive"))
      (node (ref "1R31") (pin "1") (pinfunction "1_1") (pintype "passive"))
      (node (ref "1VT5") (pin "B") (pinfunction "B_B") (pintype "passive"))
    )
    (net (code "119") (name "Net-(1R32-Pad2)") (class "Default")
      (node (ref "1R32") (pin "2") (pinfunction "2_2") (pintype "passive"))
      (node (ref "1VD3") (pin "C") (pinfunction "C_C") (pintype "passive"))
      (node (ref "1VT5") (pin "C") (pinfunction "C_C") (pintype "passive"))
      (node (ref "HW") (pin "A") (pinfunction "A_A") (pintype "passive"))
    )
    (net (code "120") (name "Net-(1R33-Pad1)") (class "Default")
      (node (ref "1R33") (pin "1") (pinfunction "1_1") (pintype "passive"))
      (node (ref "LED") (pin "A") (pinfunction "A_A") (pintype "passive"))
    )
    (net (code "121") (name "Net-(1R34-Pad1)") (class "Default")
      (node (ref "1R34") (pin "1") (pinfunction "1_1") (pintype "passive"))
      (node (ref "READY") (pin "A") (pinfunction "A_A") (pintype "passive"))
    )
    (net (code "122") (name "Net-(1R40-Pad1)") (class "Default")
      (node (ref "1R40") (pin "1") (pinfunction "1_1") (pintype "passive"))
      (node (ref "HW") (pin "C") (pinfunction "C_C") (pintype "passive"))
    )
    (net (code "123") (name "Net-(1VT4-B)") (class "Default")
      (node (ref "1R29") (pin "1") (pinfunction "1_1") (pintype "passive"))
      (node (ref "1VT4") (pin "1") (pinfunction "B_1") (pintype "passive"))
    )
    (net (code "124") (name "Net-(1VT4-C)") (class "Default")
      (node (ref "1R30") (pin "1") (pinfunction "1_1") (pintype "passive"))
      (node (ref "1VT4") (pin "3") (pinfunction "C_3") (pintype "passive"))
    )
    (net (code "125") (name "Net-(1VT6-B)") (class "Default")
      (node (ref "1R28") (pin "2") (pinfunction "2_2") (pintype "passive"))
      (node (ref "1VT6") (pin "1") (pinfunction "B_1") (pintype "passive"))
    )
    (net (code "126") (name "Net-(1X1-Pad1)") (class "Default")
      (node (ref "1X1") (pin "1") (pinfunction "1_1") (pintype "passive"))
      (node (ref "F1") (pin "2") (pinfunction "2_2") (pintype "passive"))
    )
    (net (code "127") (name "Net-(2D1-CTS_N)") (class "Default")
      (node (ref "2D1") (pin "11") (pinfunction "CTS_N_11") (pintype "bidirectional"))
      (node (ref "JI") (pin "1") (pinfunction "1_1") (pintype "passive"))
    )
    (net (code "128") (name "Net-(2D1-DCD_N)") (class "Default")
      (node (ref "2D1") (pin "10") (pinfunction "DCD_N_10") (pintype "bidirectional"))
      (node (ref "2R7") (pin "2") (pinfunction "2_2") (pintype "passive"))
    )
    (net (code "129") (name "Net-(2D1-DM)") (class "Default")
      (node (ref "2D1") (pin "16") (pinfunction "DM_16") (pintype "bidirectional"))
      (node (ref "2R1") (pin "2") (pinfunction "2_2") (pintype "passive"))
    )
    (net (code "130") (name "Net-(2D1-DP)") (class "Default")
      (node (ref "2D1") (pin "15") (pinfunction "DP_15") (pintype "bidirectional"))
      (node (ref "2R8") (pin "2") (pinfunction "2_2") (pintype "passive"))
    )
    (net (code "131") (name "Net-(2D1-DSR_N)") (class "Default")
      (node (ref "2D1") (pin "9") (pinfunction "DSR_N_9") (pintype "bidirectional"))
      (node (ref "2R6") (pin "2") (pinfunction "2_2") (pintype "passive"))
    )
    (net (code "132") (name "Net-(2D1-DTR_N)") (class "Default")
      (node (ref "2D1") (pin "2") (pinfunction "DTR_N_2") (pintype "bidirectional"))
      (node (ref "JO") (pin "1") (pinfunction "1_1") (pintype "passive"))
    )
    (net (code "133") (name "Net-(2D1-EE_CLK)") (class "Default")
      (node (ref "2D1") (pin "13") (pinfunction "EE_CLK_13") (pintype "bidirectional"))
      (node (ref "2D2") (pin "6") (pinfunction "SCL_6") (pintype "input"))
      (node (ref "2R10") (pin "1") (pinfunction "1_1") (pintype "passive"))
    )
    (net (code "134") (name "Net-(2D1-EE_DATA)") (class "Default")
      (node (ref "2D1") (pin "14") (pinfunction "EE_DATA_14") (pintype "bidirectional"))
      (node (ref "2R9") (pin "1") (pinfunction "1_1") (pintype "passive"))
      (node (ref "JD") (pin "2") (pinfunction "2_2") (pintype "passive"))
    )
    (net (code "135") (name "Net-(2D1-GP0)") (class "Default")
      (node (ref "2D1") (pin "22") (pinfunction "GP0_22") (pintype "bidirectional"))
      (node (ref "2R3") (pin "2") (pinfunction "2_2") (pintype "passive"))
    )
    (net (code "136") (name "Net-(2D1-GP1)") (class "Default")
      (node (ref "2D1") (pin "23") (pinfunction "GP1_23") (pintype "bidirectional"))
      (node (ref "2R2") (pin "2") (pinfunction "2_2") (pintype "passive"))
    )
    (net (code "137") (name "Net-(2D1-OSC1)") (class "Default")
      (node (ref "2C2") (pin "2") (pinfunction "2_2") (pintype "passive"))
      (node (ref "2D1") (pin "27") (pinfunction "OSC1_27") (pintype "bidirectional"))
      (node (ref "2Z1") (pin "1") (pinfunction "1_1") (pintype "passive"))
    )
    (net (code "138") (name "Net-(2D1-OSC2)") (class "Default")
      (node (ref "2C1") (pin "2") (pinfunction "2_2") (pintype "passive"))
      (node (ref "2D1") (pin "28") (pinfunction "OSC2_28") (pintype "bidirectional"))
      (node (ref "2Z1") (pin "2") (pinfunction "2_2") (pintype "passive"))
    )
    (net (code "139") (name "Net-(2D1-RI_N)") (class "Default")
      (node (ref "2D1") (pin "6") (pinfunction "RI_N_6") (pintype "bidirectional"))
      (node (ref "2R5") (pin "1") (pinfunction "1_1") (pintype "passive"))
    )
    (net (code "140") (name "Net-(2D1-RTS_N)") (class "Default")
      (node (ref "2D1") (pin "3") (pinfunction "RTS_N_3") (pintype "bidirectional"))
      (node (ref "JS") (pin "1") (pinfunction "1_1") (pintype "passive"))
    )
    (net (code "141") (name "Net-(2D1-VDD_325)") (class "Default")
      (node (ref "2C3") (pin "1") (pinfunction "1_1") (pintype "passive"))
      (node (ref "2D1") (pin "17") (pinfunction "VO_33_17") (pintype "bidirectional"))
      (node (ref "2D1") (pin "4") (pinfunction "VDD_325_4") (pintype "bidirectional"))
      (node (ref "2D2") (pin "8") (pinfunction "VCC_8") (pintype "power_in"))
      (node (ref "2R10") (pin "2") (pinfunction "2_2") (pintype "passive"))
      (node (ref "2R4") (pin "1") (pinfunction "1_1") (pintype "passive"))
      (node (ref "2R9") (pin "2") (pinfunction "2_2") (pintype "passive"))
    )
    (net (code "142") (name "Net-(2D2-SDA)") (class "Default")
      (node (ref "2D2") (pin "5") (pinfunction "SDA_5") (pintype "bidirectional"))
      (node (ref "JD") (pin "1") (pinfunction "1_1") (pintype "passive"))
    )
    (net (code "143") (name "Net-(2D2-WP)") (class "Default")
      (node (ref "2D2") (pin "7") (pinfunction "WP_7") (pintype "input"))
      (node (ref "JWP") (pin "2") (pinfunction "2_2") (pintype "passive"))
    )
    (net (code "144") (name "Net-(4C2-Pad2)") (class "Default")
      (node (ref "4C2") (pin "2") (pinfunction "2_2") (pintype "passive"))
      (node (ref "4R8") (pin "1") (pinfunction "1_1") (pintype "passive"))
      (node (ref "4R9") (pin "2") (pinfunction "2_2") (pintype "passive"))
    )
    (net (code "145") (name "Net-(4D1-D+)") (class "Default")
      (node (ref "4D1") (pin "4") (pinfunction "D+_4") (pintype "bidirectional"))
      (node (ref "U_U2") (pin "2") (pinfunction "2_2") (pintype "passive"))
      (node (ref "U_U3") (pin "2") (pinfunction "2_2") (pintype "passive"))
    )
    (net (code "146") (name "Net-(4D1-D-)") (class "Default")
      (node (ref "4D1") (pin "3") (pinfunction "D-_3") (pintype "bidirectional"))
      (node (ref "U_U1") (pin "2") (pinfunction "2_2") (pintype "passive"))
      (node (ref "U_U4") (pin "2") (pinfunction "2_2") (pintype "passive"))
    )
    (net (code "147") (name "Net-(4VT4-B)") (class "Default")
      (node (ref "4R7") (pin "2") (pinfunction "2_2") (pintype "passive"))
      (node (ref "4R8") (pin "2") (pinfunction "2_2") (pintype "passive"))
      (node (ref "4VT4") (pin "1") (pinfunction "B_1") (pintype "passive"))
    )
    (net (code "148") (name "Net-(4VT4-C)") (class "Default")
      (node (ref "4R6") (pin "2") (pinfunction "2_2") (pintype "passive"))
      (node (ref "4VT4") (pin "3") (pinfunction "C_3") (pintype "passive"))
      (node (ref "4VT5") (pin "1") (pinfunction "G_1") (pintype "passive"))
    )
    (net (code "149") (name "Net-(4VT6-G)") (class "Default")
      (node (ref "4R10") (pin "2") (pinfunction "2_2") (pintype "passive"))
      (node (ref "4VT6") (pin "1") (pinfunction "G_1") (pintype "passive"))
    )
    (net (code "150") (name "Net-(5D1-(ADC4)PA4)") (class "Default")
      (node (ref "5D1") (pin "33") (pinfunction "(ADC4)PA4_33") (pintype "bidirectional"))
      (node (ref "5D2") (pin "1") (pinfunction "SH/~{LD}_1") (pintype "input"))
      (node (ref "LED") (pin "C") (pinfunction "C_C") (pintype "passive"))
    )
    (net (code "151") (name "Net-(5D1-(ADC5)PA5)") (class "Default")
      (node (ref "5D1") (pin "32") (pinfunction "(ADC5)PA5_32") (pintype "bidirectional"))
      (node (ref "5D2") (pin "2") (pinfunction "CLK_2") (pintype "input"))
      (node (ref "READY") (pin "C") (pinfunction "C_C") (pintype "passive"))
    )
    (net (code "152") (name "Net-(5D1-(ADC6)PA6)") (class "Default")
      (node (ref "1R35") (pin "1") (pinfunction "1_1") (pintype "passive"))
      (node (ref "1R36") (pin "2") (pinfunction "2_2") (pintype "passive"))
      (node (ref "5D1") (pin "30") (pinfunction "(ADC7)PA7_30") (pintype "bidirectional"))
      (node (ref "5D1") (pin "31") (pinfunction "(ADC6)PA6_31") (pintype "bidirectional"))
    )
    (net (code "153") (name "Net-(5D1-(ICP)PD6)") (class "Default")
      (node (ref "5D1") (pin "15") (pinfunction "(ICP)PD6_15") (pintype "bidirectional"))
      (node (ref "5D2") (pin "9") (pinfunction "QH_9") (pintype "output"))
    )
    (net (code "154") (name "Net-(5D1-(INT1)PD3)") (class "Default")
      (node (ref "5D1") (pin "12") (pinfunction "(INT1)PD3_12") (pintype "bidirectional"))
      (node (ref "HW1") (pin "1") (pinfunction "1_1") (pintype "passive"))
    )
    (net (code "155") (name "Net-(5D1-XTAL1)") (class "Default")
      (node (ref "1C21") (pin "2") (pinfunction "2_2") (pintype "passive"))
      (node (ref "5D1") (pin "8") (pinfunction "XTAL1_8") (pintype "bidirectional"))
      (node (ref "Z3") (pin "1") (pinfunction "1_1") (pintype "passive"))
    )
    (net (code "156") (name "Net-(5D1-XTAL2)") (class "Default")
      (node (ref "1C20") (pin "2") (pinfunction "2_2") (pintype "passive"))
      (node (ref "5D1") (pin "7") (pinfunction "XTAL2_7") (pintype "bidirectional"))
      (node (ref "Z3") (pin "2") (pinfunction "2_2") (pintype "passive"))
    )
    (net (code "157") (name "Net-(5D2A-A)") (class "Default")
      (node (ref "1R38") (pin "2") (pinfunction "2_2") (pintype "passive"))
      (node (ref "5D2") (pin "11") (pinfunction "A_11") (pintype "input"))
      (node (ref "5D2") (pin "13") (pinfunction "C_13") (pintype "input"))
      (node (ref "5D2") (pin "14") (pinfunction "D_14") (pintype "input"))
    )
    (net (code "158") (name "Net-(5D2A-B)") (class "Default")
      (node (ref "1R37") (pin "2") (pinfunction "2_2") (pintype "passive"))
      (node (ref "5D2") (pin "12") (pinfunction "B_12") (pintype "input"))
      (node (ref "5D2") (pin "3") (pinfunction "E_3") (pintype "input"))
      (node (ref "5D2") (pin "4") (pinfunction "F_4") (pintype "input"))
      (node (ref "5D2") (pin "5") (pinfunction "G_5") (pintype "input"))
    )
    (net (code "159") (name "Net-(5D2A-H)") (class "Default")
      (node (ref "1R39") (pin "2") (pinfunction "2_2") (pintype "passive"))
      (node (ref "5D2") (pin "6") (pinfunction "H_6") (pintype "input"))
      (node (ref "T_RESET") (pin "1") (pinfunction "1_1") (pintype "passive"))
    )
    (net (code "160") (name "Net-(5D3-DC)") (class "Default")
      (node (ref "3R5") (pin "1") (pinfunction "1_1") (pintype "passive"))
      (node (ref "5D3") (pin "8") (pinfunction "DC_8") (pintype "passive"))
    )
    (net (code "161") (name "Net-(5D3-FB)") (class "Default")
      (node (ref "3R7") (pin "1") (pinfunction "1_1") (pintype "passive"))
      (node (ref "3R8") (pin "2") (pinfunction "2_2") (pintype "passive"))
      (node (ref "5D3") (pin "5") (pinfunction "FB_5") (pintype "passive"))
    )
    (net (code "162") (name "Net-(5D3-IS)") (class "Default")
      (node (ref "3L2") (pin "1") (pinfunction "1_1") (pintype "passive"))
      (node (ref "3R5") (pin "2") (pinfunction "2_2") (pintype "passive"))
      (node (ref "3R6") (pin "2") (pinfunction "2_2") (pintype "passive"))
      (node (ref "5D3") (pin "7") (pinfunction "IS_7") (pintype "passive"))
    )
    (net (code "163") (name "Net-(5D3-SWC)") (class "Default")
      (node (ref "3L2") (pin "2") (pinfunction "2_2") (pintype "passive"))
      (node (ref "3VD2") (pin "A") (pinfunction "A_A") (pintype "passive"))
      (node (ref "5D3") (pin "1") (pinfunction "SWC_1") (pintype "passive"))
    )
    (net (code "164") (name "Net-(5D3-TC)") (class "Default")
      (node (ref "3C7") (pin "1") (pinfunction "1_1") (pintype "passive"))
      (node (ref "5D3") (pin "3") (pinfunction "TC_3") (pintype "passive"))
    )
    (net (code "165") (name "Net-(5D4A-A3)") (class "Default")
      (node (ref "5D4") (pin "6") (pinfunction "A3_6") (pintype "input"))
      (node (ref "5D4") (pin "7") (pinfunction "Y2_7") (pintype "tri_state"))
    )
    (net (code "166") (name "Net-(5D4A-G)") (class "Default")
      (node (ref "1R17") (pin "2") (pinfunction "2_2") (pintype "passive"))
      (node (ref "5D4") (pin "1") (pinfunction "G_1") (pintype "input"))
      (node (ref "D11") (pin "C") (pinfunction "C_C") (pintype "passive"))
      (node (ref "D8") (pin "C") (pinfunction "C_C") (pintype "passive"))
      (node (ref "D9") (pin "C") (pinfunction "C_C") (pintype "passive"))
    )
    (net (code "167") (name "Net-(5D4B-G)") (class "Default")
      (node (ref "1R14") (pin "2") (pinfunction "2_2") (pintype "passive"))
      (node (ref "5D4") (pin "19") (pinfunction "G_19") (pintype "input"))
      (node (ref "D10") (pin "C") (pinfunction "C_C") (pintype "passive"))
      (node (ref "D6") (pin "C") (pinfunction "C_C") (pintype "passive"))
      (node (ref "D7") (pin "C") (pinfunction "C_C") (pintype "passive"))
    )
    (net (code "168") (name "Net-(5D5A-O)") (class "Default")
      (node (ref "5D5") (pin "3") (pinfunction "O_3") (pintype "output"))
      (node (ref "5D5") (pin "5") (pinfunction "I0_5") (pintype "input"))
      (node (ref "5D5") (pin "6") (pinfunction "I1_6") (pintype "input"))
    )
    (net (code "169") (name "Net-(5D5B-O)") (class "Default")
      (node (ref "5D5") (pin "4") (pinfunction "O_4") (pintype "output"))
      (node (ref "D10") (pin "A") (pinfunction "A_A") (pintype "passive"))
      (node (ref "D11") (pin "A") (pinfunction "A_A") (pintype "passive"))
    )
    (net (code "170") (name "Net-(5D5C-O)") (class "Default")
      (node (ref "5D5") (pin "10") (pinfunction "O_10") (pintype "output"))
      (node (ref "5D6") (pin "19") (pinfunction "G_19") (pintype "input"))
    )
    (net (code "171") (name "Net-(5D6A-A3)") (class "Default")
      (node (ref "5D6") (pin "6") (pinfunction "A3_6") (pintype "input"))
      (node (ref "5D6") (pin "7") (pinfunction "Y2_7") (pintype "tri_state"))
    )
    (net (code "172") (name "Net-(5D6A-A4)") (class "Default")
      (node (ref "5D6") (pin "8") (pinfunction "A4_8") (pintype "input"))
      (node (ref "JRX") (pin "2") (pinfunction "2_2") (pintype "passive"))
    )
    (net (code "173") (name "Net-(5D6A-Y2)") (class "Default")
      (node (ref "5D6") (pin "13") (pinfunction "A2_13") (pintype "input"))
      (node (ref "5D6") (pin "15") (pinfunction "A3_15") (pintype "input"))
      (node (ref "5D6") (pin "16") (pinfunction "Y2_16") (pintype "tri_state"))
      (node (ref "JTX") (pin "1") (pinfunction "1_1") (pintype "passive"))
    )
    (net (code "174") (name "Net-(R2-Pad2)") (class "Default")
      (node (ref "R2") (pin "2") (pinfunction "2_2") (pintype "passive"))
      (node (ref "RESET") (pin "A") (pinfunction "A_A") (pintype "passive"))
    )
    (net (code "175") (name "VUSB") (class "Default")
      (node (ref "1C7") (pin "+") (pinfunction "+_+") (pintype "passive"))
      (node (ref "1C8") (pin "2") (pinfunction "2_2") (pintype "passive"))
      (node (ref "1C9") (pin "2") (pinfunction "2_2") (pintype "passive"))
      (node (ref "1D1") (pin "20") (pinfunction "VDD5_20") (pintype "bidirectional"))
      (node (ref "1R6") (pin "2") (pinfunction "2_2") (pintype "passive"))
      (node (ref "4D1") (pin "7") (pinfunction "VBUS_7") (pintype "input"))
      (node (ref "F1") (pin "1") (pinfunction "1_1") (pintype "passive"))
    )
    (net (code "176") (name "unconnected-(1D1-PWRJ-Pad25)") (class "Default")
      (node (ref "1D1") (pin "25") (pinfunction "PWRJ_25") (pintype "bidirectional"))
    )
    (net (code "177") (name "unconnected-(2D1-SHTD_N-Pad12)") (class "Default")
      (node (ref "2D1") (pin "12") (pinfunction "SHTD_N_12") (pintype "bidirectional"))
    )
    (net (code "178") (name "unconnected-(5D1-(ADC0)PA0-Pad37)") (class "Default")
      (node (ref "5D1") (pin "37") (pinfunction "(ADC0)PA0_37") (pintype "bidirectional"))
    )
    (net (code "179") (name "unconnected-(5D1-(ADC1)PA1-Pad36)") (class "Default")
      (node (ref "5D1") (pin "36") (pinfunction "(ADC1)PA1_36") (pintype "bidirectional"))
    )
    (net (code "180") (name "unconnected-(5D1-(ADC2)PA2-Pad35)") (class "Default")
      (node (ref "5D1") (pin "35") (pinfunction "(ADC2)PA2_35") (pintype "bidirectional"))
    )
    (net (code "181") (name "unconnected-(5D1-(ADC3)PA3-Pad34)") (class "Default")
      (node (ref "5D1") (pin "34") (pinfunction "(ADC3)PA3_34") (pintype "bidirectional"))
    )
    (net (code "182") (name "unconnected-(5D1-(OC1B)PD4-Pad13)") (class "Default")
      (node (ref "5D1") (pin "13") (pinfunction "(OC1B)PD4_13") (pintype "bidirectional"))
    )
    (net (code "183") (name "unconnected-(5D2A-~{QH}-Pad7)") (class "Default")
      (node (ref "5D2") (pin "7") (pinfunction "~{QH}_7") (pintype "output"))
    )
    (net (code "184") (name "unconnected-(5D4A-Y3-Pad14)") (class "Default")
      (node (ref "5D4") (pin "14") (pinfunction "Y3_14") (pintype "tri_state"))
    )
    (net (code "185") (name "unconnected-(5D5D-O-Pad11)") (class "Default")
      (node (ref "5D5") (pin "11") (pinfunction "O_11") (pintype "output"))
    )
    (net (code "186") (name "unconnected-(5D6A-Y1-Pad18)") (class "Default")
      (node (ref "5D6") (pin "18") (pinfunction "Y1_18") (pintype "tri_state"))
    )
    (net (code "187") (name "unconnected-(5D6A-Y3-Pad14)") (class "Default")
      (node (ref "5D6") (pin "14") (pinfunction "Y3_14") (pintype "tri_state"))
    )
    (net (code "188") (name "unconnected-(5D6B-Y3-Pad5)") (class "Default")
      (node (ref "5D6") (pin "5") (pinfunction "Y3_5") (pintype "tri_state"))
    )
    (net (code "189") (name "unconnected-(RNC-1-Pad3)") (class "Default")
      (node (ref "RN") (pin "3") (pinfunction "1_3") (pintype "passive"))
    )
    (net (code "190") (name "unconnected-(RNC-2-Pad6)") (class "Default")
      (node (ref "RN") (pin "6") (pinfunction "2_6") (pintype "passive"))
    )
    (net (code "191") (name "unconnected-(RND-1-Pad4)") (class "Default")
      (node (ref "RN") (pin "4") (pinfunction "1_4") (pintype "passive"))
    )
    (net (code "192") (name "unconnected-(RND-2-Pad5)") (class "Default")
      (node (ref "RN") (pin "5") (pinfunction "2_5") (pintype "passive"))
    )
    (net (code "193") (name "unconnected-(SV1-Pad1)") (class "Default")
      (node (ref "SV1") (pin "1") (pinfunction "1_1") (pintype "passive"))
    )
    (net (code "194") (name "unconnected-(SV1-Pad2)") (class "Default")
      (node (ref "SV1") (pin "2") (pinfunction "2_2") (pintype "passive"))
    )
    (net (code "195") (name "unconnected-(SV1-Pad3)") (class "Default")
      (node (ref "SV1") (pin "3") (pinfunction "3_3") (pintype "passive"))
    )
    (net (code "196") (name "unconnected-(SV1-Pad4)") (class "Default")
      (node (ref "SV1") (pin "4") (pinfunction "4_4") (pintype "passive"))
    )
    (net (code "197") (name "unconnected-(SV1-Pad5)") (class "Default")
      (node (ref "SV1") (pin "5") (pinfunction "5_5") (pintype "passive"))
    )
    (net (code "198") (name "unconnected-(SV1-Pad6)") (class "Default")
      (node (ref "SV1") (pin "6") (pinfunction "6_6") (pintype "passive"))
    )
    (net (code "199") (name "unconnected-(SV1-Pad7)") (class "Default")
      (node (ref "SV1") (pin "7") (pinfunction "7_7") (pintype "passive"))
    )
    (net (code "200") (name "unconnected-(SV1-Pad8)") (class "Default")
      (node (ref "SV1") (pin "8") (pinfunction "8_8") (pintype "passive"))
    )
    (net (code "201") (name "unconnected-(SV1-Pad9)") (class "Default")
      (node (ref "SV1") (pin "9") (pinfunction "9_9") (pintype "passive"))
    )
    (net (code "202") (name "unconnected-(SV1-Pad10)") (class "Default")
      (node (ref "SV1") (pin "10") (pinfunction "10_10") (pintype "passive"))
    )
    (net (code "203") (name "unconnected-(SV1-Pad11)") (class "Default")
      (node (ref "SV1") (pin "11") (pinfunction "11_11") (pintype "passive"))
    )
    (net (code "204") (name "unconnected-(SV2-Pad1)") (class "Default")
      (node (ref "SV2") (pin "1") (pinfunction "1_1") (pintype "passive"))
    )
    (net (code "205") (name "unconnected-(SV2-Pad2)") (class "Default")
      (node (ref "SV2") (pin "2") (pinfunction "2_2") (pintype "passive"))
    )
    (net (code "206") (name "unconnected-(SV2-Pad3)") (class "Default")
      (node (ref "SV2") (pin "3") (pinfunction "3_3") (pintype "passive"))
    )
    (net (code "207") (name "unconnected-(SV3-Pad1)") (class "Default")
      (node (ref "SV3") (pin "1") (pinfunction "1_1") (pintype "passive"))
    )
    (net (code "208") (name "unconnected-(SV3-Pad2)") (class "Default")
      (node (ref "SV3") (pin "2") (pinfunction "2_2") (pintype "passive"))
    )
    (net (code "209") (name "unconnected-(SV3-Pad3)") (class "Default")
      (node (ref "SV3") (pin "3") (pinfunction "3_3") (pintype "passive"))
    )
    (net (code "210") (name "unconnected-(SV3-Pad4)") (class "Default")
      (node (ref "SV3") (pin "4") (pinfunction "4_4") (pintype "passive"))
    )
    (net (code "211") (name "unconnected-(SV3-Pad5)") (class "Default")
      (node (ref "SV3") (pin "5") (pinfunction "5_5") (pintype "passive"))
    )
    (net (code "212") (name "unconnected-(SV3-Pad6)") (class "Default")
      (node (ref "SV3") (pin "6") (pinfunction "6_6") (pintype "passive"))
    )
    (net (code "213") (name "unconnected-(SV3-Pad7)") (class "Default")
      (node (ref "SV3") (pin "7") (pinfunction "7_7") (pintype "passive"))
    )
    (net (code "214") (name "unconnected-(SV3-Pad8)") (class "Default")
      (node (ref "SV3") (pin "8") (pinfunction "8_8") (pintype "passive"))
    )
    (net (code "215") (name "unconnected-(SV6-Pad8)") (class "Default")
      (node (ref "SV6") (pin "8") (pinfunction "8_8") (pintype "passive"))
    )
    (net (code "216") (name "unconnected-(SV6-Pad10)") (class "Default")
      (node (ref "SV6") (pin "10") (pinfunction "10_10") (pintype "passive"))
    )
  )
)
